# stm32_v0_7_eagle_v7.net
KiCad netlist of a schematic drawn in EAGLE
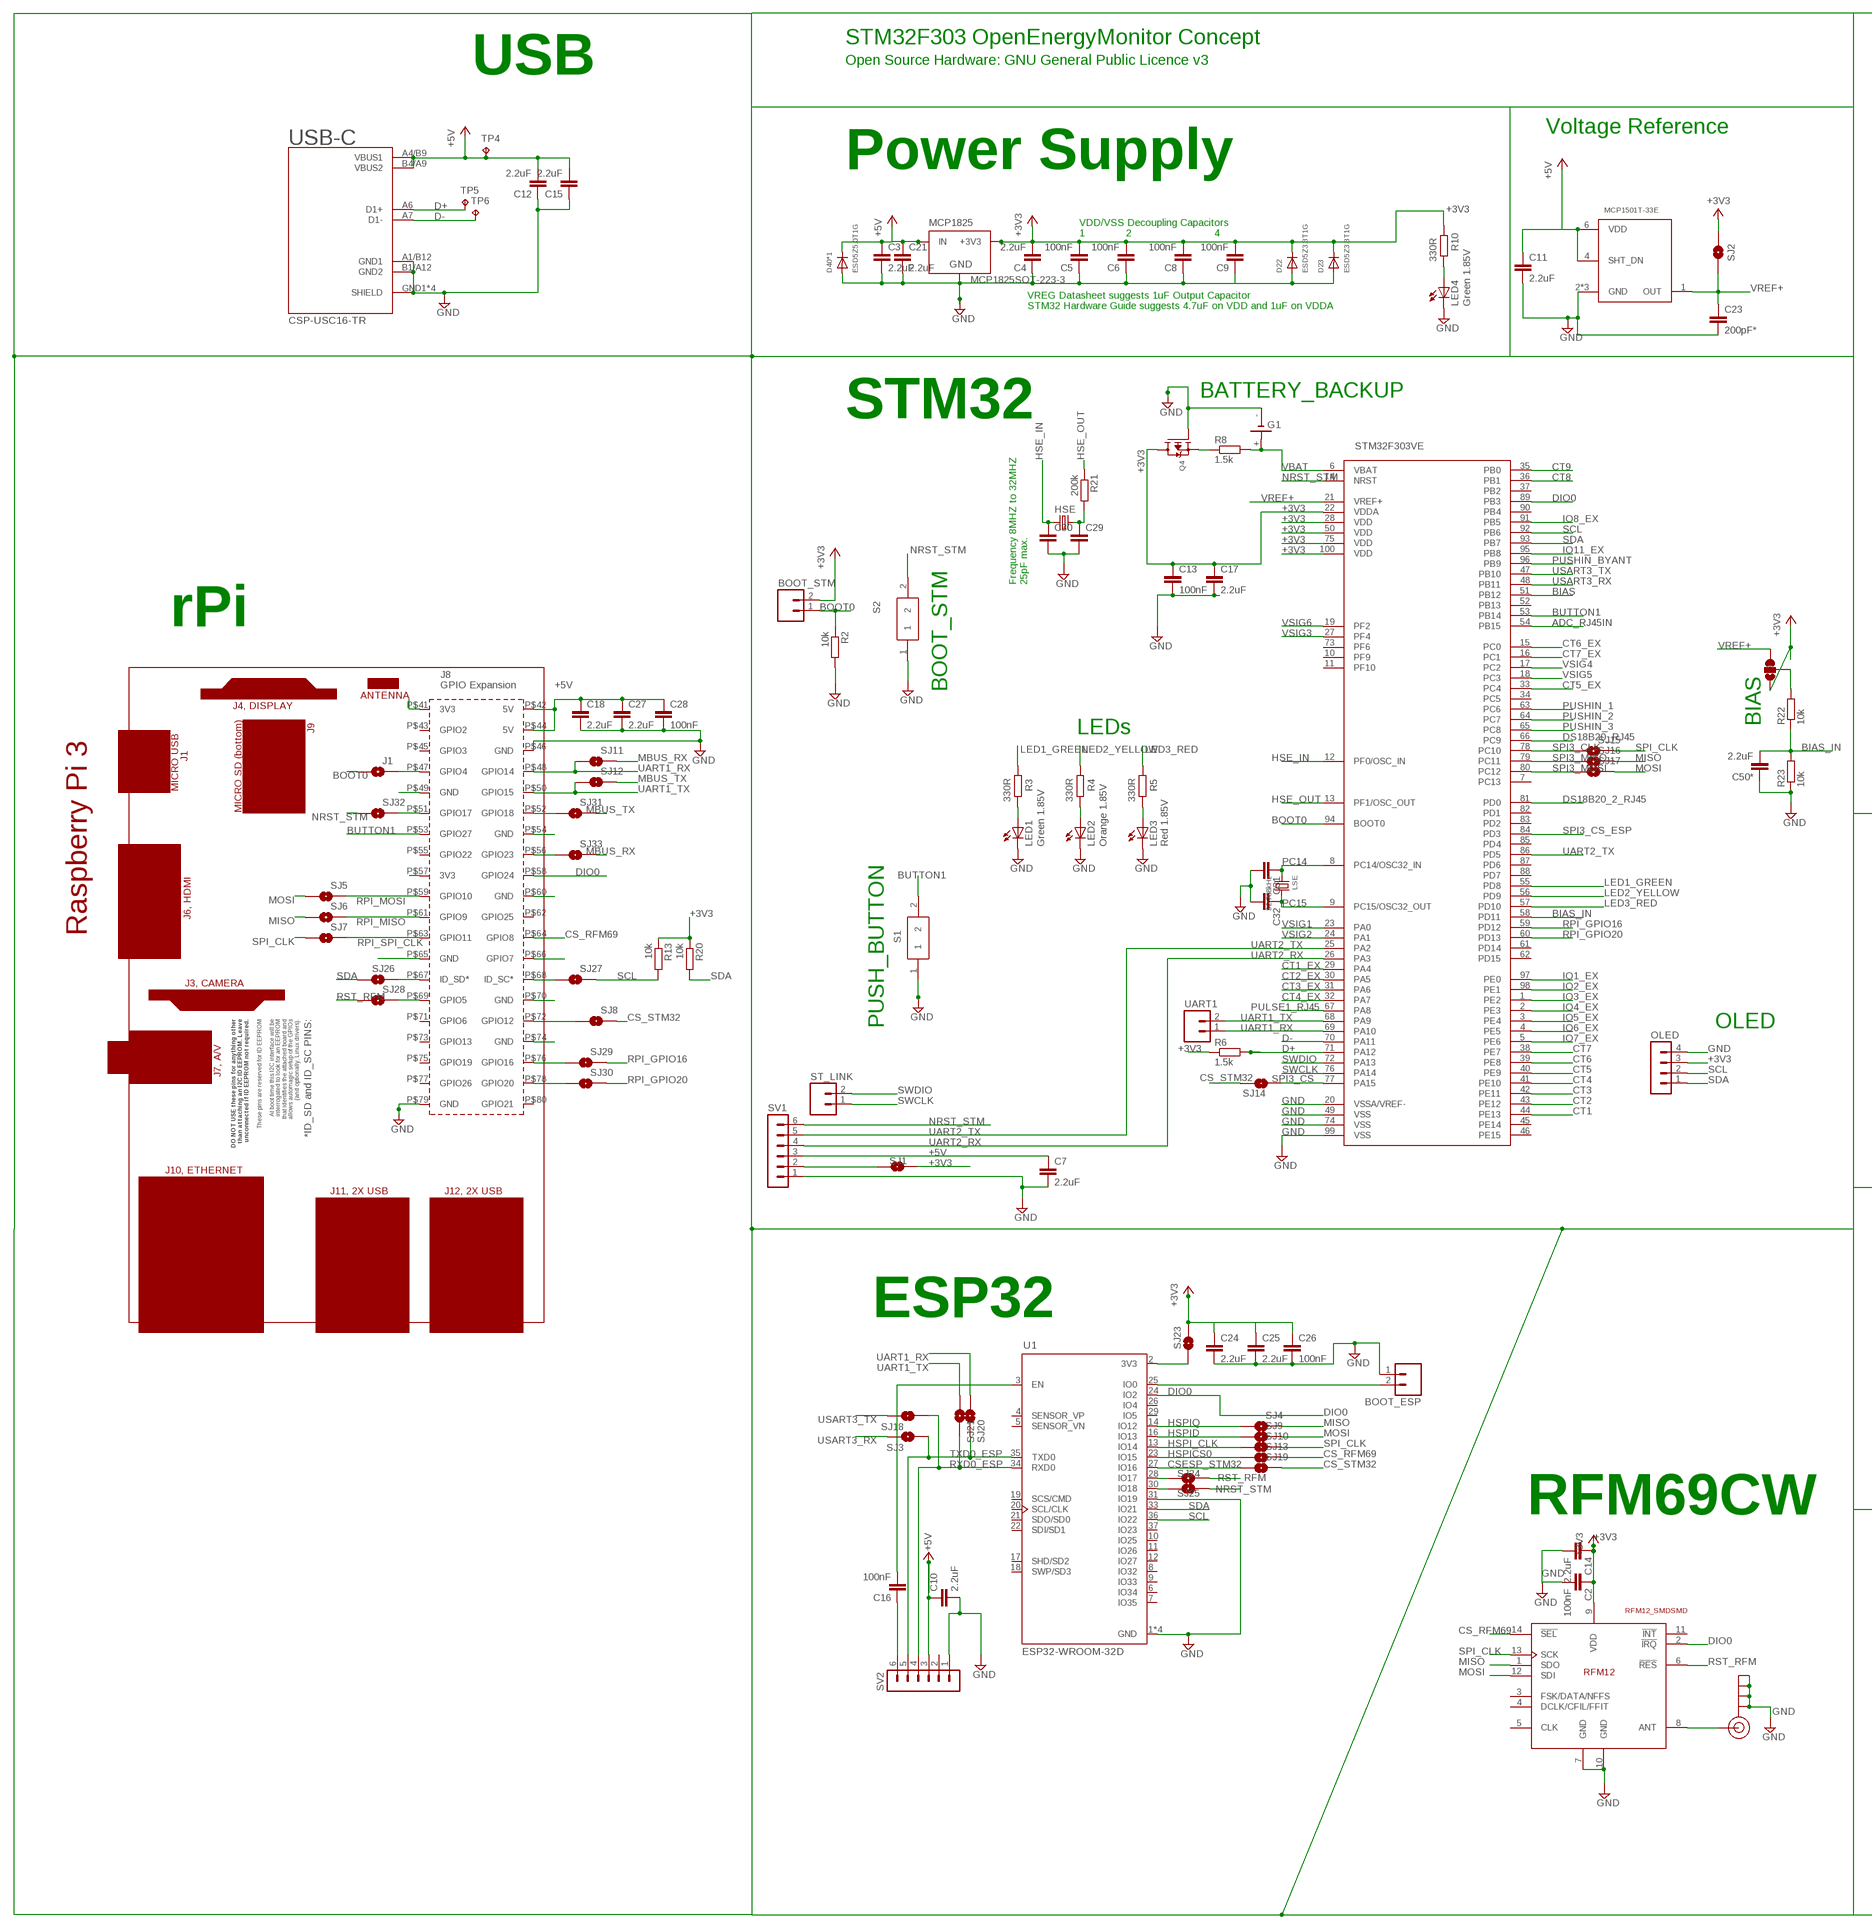
[diagram p0: schematic, sheet 1, part 1 of 2]
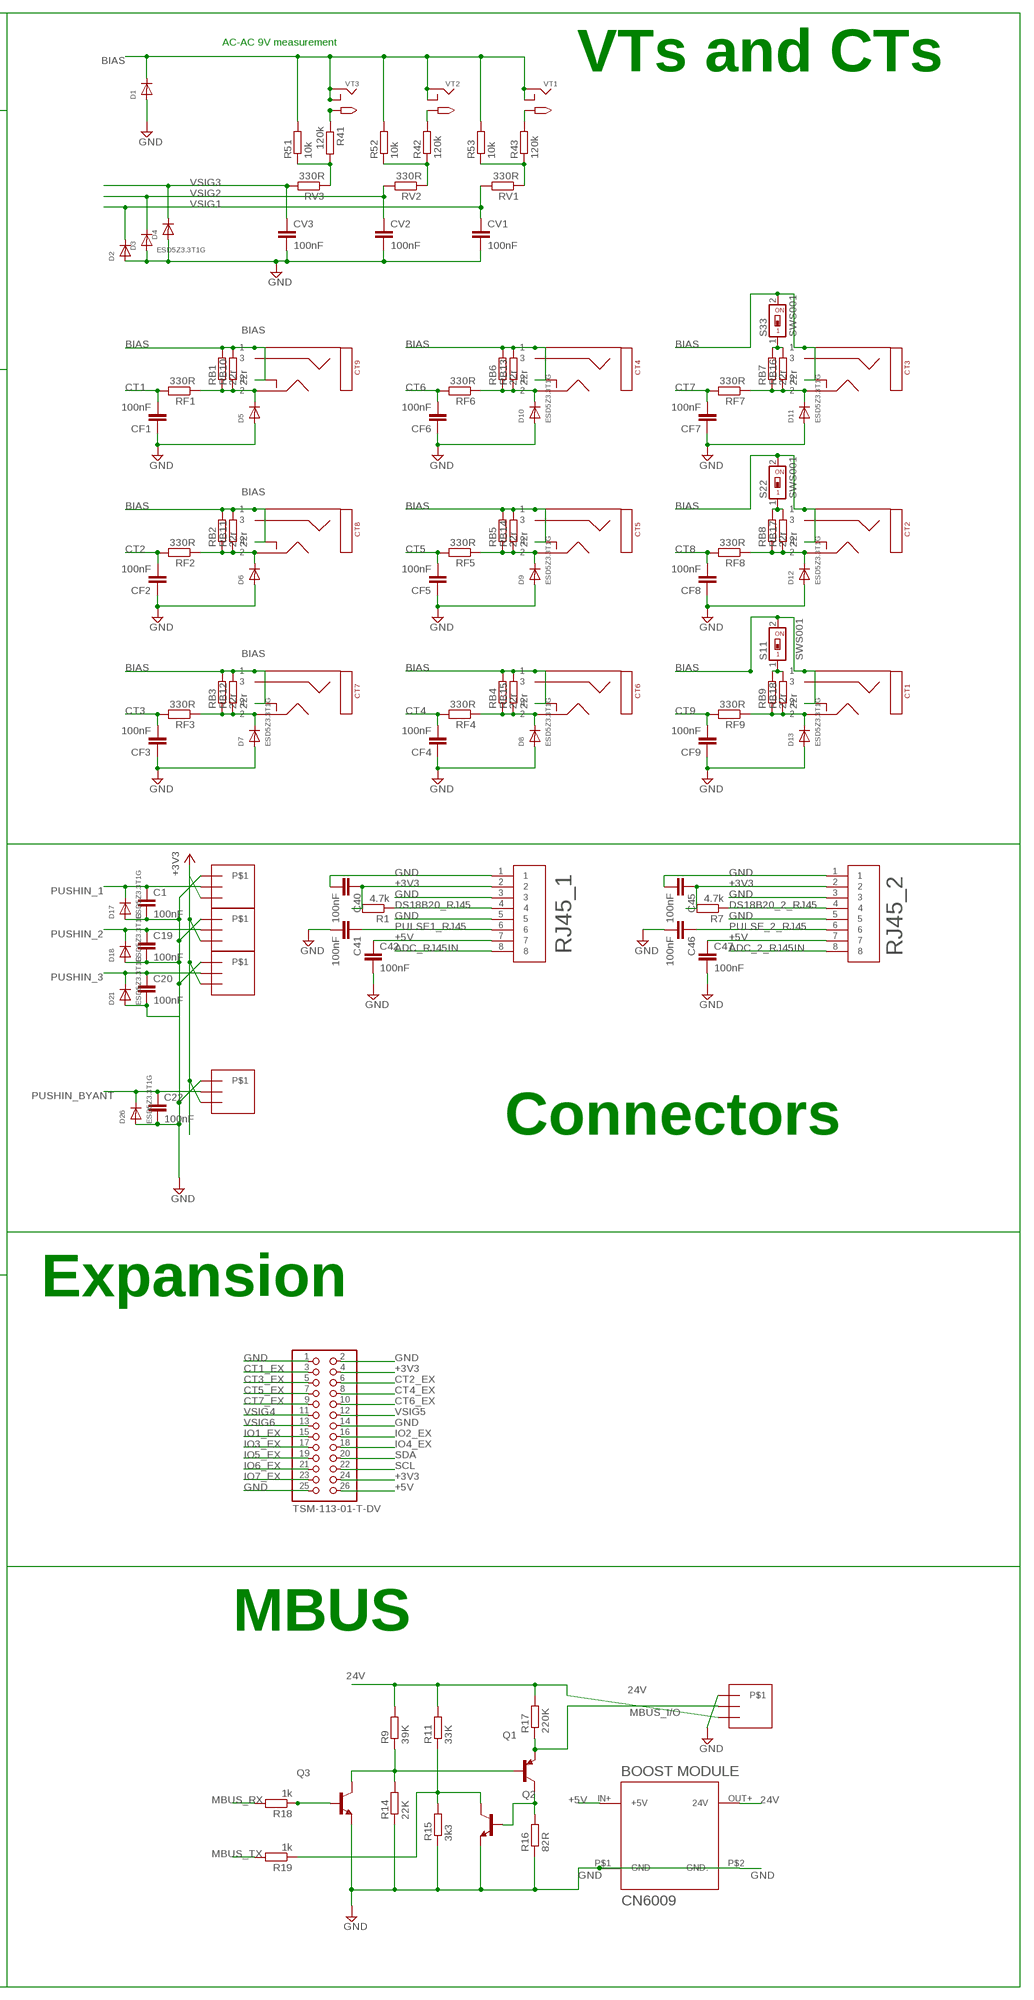
[diagram p1: schematic, sheet 1, part 2 of 2]

(export (version "E")
  (design (tool "Eeschema 10.0.6"))
  (components
    (comp (ref "BOOT_ESP")
      (value "M02PTH")
      (footprint "eagle-import:1X02")
      (libsource (lib "eagle-import") (part "M02PTH"))
    )
    (comp (ref "BOOT_STM")
      (value "M02PTH")
      (footprint "eagle-import:1X02")
      (libsource (lib "eagle-import") (part "M02PTH"))
    )
    (comp (ref "C1")
      (value "100nF")
      (footprint "eagle-import:C0603")
      (libsource (lib "eagle-import") (part "resistor_C-EUC0603"))
    )
    (comp (ref "C2")
      (value "100nF")
      (footprint "eagle-import:C0603")
      (libsource (lib "eagle-import") (part "resistor_C-EUC0603"))
    )
    (comp (ref "C3")
      (value "2.2uF")
      (footprint "eagle-import:C0805")
      (libsource (lib "eagle-import") (part "C-EUC0805"))
    )
    (comp (ref "C4")
      (value "2.2uF")
      (footprint "eagle-import:C0805")
      (libsource (lib "eagle-import") (part "C-EUC0805"))
    )
    (comp (ref "C5")
      (value "100nF")
      (footprint "eagle-import:C0603")
      (libsource (lib "eagle-import") (part "resistor_C-EUC0603"))
    )
    (comp (ref "C6")
      (value "100nF")
      (footprint "eagle-import:C0603")
      (libsource (lib "eagle-import") (part "resistor_C-EUC0603"))
    )
    (comp (ref "C7")
      (value "2.2uF")
      (footprint "eagle-import:C0805")
      (libsource (lib "eagle-import") (part "C-EUC0805"))
    )
    (comp (ref "C8")
      (value "100nF")
      (footprint "eagle-import:C0603")
      (libsource (lib "eagle-import") (part "resistor_C-EUC0603"))
    )
    (comp (ref "C9")
      (value "100nF")
      (footprint "eagle-import:C0603")
      (libsource (lib "eagle-import") (part "resistor_C-EUC0603"))
    )
    (comp (ref "C10")
      (value "2.2uF")
      (footprint "eagle-import:C0805")
      (libsource (lib "eagle-import") (part "C-EUC0805"))
    )
    (comp (ref "C11")
      (value "2.2uF")
      (footprint "eagle-import:C0805")
      (libsource (lib "eagle-import") (part "C-EUC0805"))
    )
    (comp (ref "C12")
      (value "2.2uF")
      (footprint "eagle-import:C0805")
      (libsource (lib "eagle-import") (part "C-EUC0805"))
    )
    (comp (ref "C13")
      (value "100nF")
      (footprint "eagle-import:C0603")
      (libsource (lib "eagle-import") (part "C-EUC0603"))
    )
    (comp (ref "C14")
      (value "2.2uF")
      (footprint "eagle-import:C0805")
      (libsource (lib "eagle-import") (part "C-EUC0805"))
    )
    (comp (ref "C15")
      (value "2.2uF")
      (footprint "eagle-import:C0805")
      (libsource (lib "eagle-import") (part "C-EUC0805"))
    )
    (comp (ref "C16")
      (value "100nF")
      (footprint "eagle-import:C0603")
      (libsource (lib "eagle-import") (part "resistor_C-EUC0603"))
    )
    (comp (ref "C17")
      (value "2.2uF")
      (footprint "eagle-import:C0805")
      (libsource (lib "eagle-import") (part "C-EUC0805"))
    )
    (comp (ref "C18")
      (value "2.2uF")
      (footprint "eagle-import:C0805")
      (libsource (lib "eagle-import") (part "C-EUC0805"))
    )
    (comp (ref "C19")
      (value "100nF")
      (footprint "eagle-import:C0603")
      (libsource (lib "eagle-import") (part "resistor_C-EUC0603"))
    )
    (comp (ref "C20")
      (value "100nF")
      (footprint "eagle-import:C0603")
      (libsource (lib "eagle-import") (part "resistor_C-EUC0603"))
    )
    (comp (ref "C21")
      (value "2.2uF")
      (footprint "eagle-import:C0805")
      (libsource (lib "eagle-import") (part "C-EUC0805"))
    )
    (comp (ref "C22")
      (value "100nF")
      (footprint "eagle-import:C0603")
      (libsource (lib "eagle-import") (part "resistor_C-EUC0603"))
    )
    (comp (ref "C23")
      (value "200pF*")
      (footprint "eagle-import:C0603")
      (libsource (lib "eagle-import") (part "C-EUC0603"))
    )
    (comp (ref "C24")
      (value "2.2uF")
      (footprint "eagle-import:C0805")
      (libsource (lib "eagle-import") (part "C-EUC0805"))
    )
    (comp (ref "C25")
      (value "2.2uF")
      (footprint "eagle-import:C0805")
      (libsource (lib "eagle-import") (part "C-EUC0805"))
    )
    (comp (ref "C26")
      (value "100nF")
      (footprint "eagle-import:C0603")
      (libsource (lib "eagle-import") (part "resistor_C-EUC0603"))
    )
    (comp (ref "C27")
      (value "2.2uF")
      (footprint "eagle-import:C0805")
      (libsource (lib "eagle-import") (part "C-EUC0805"))
    )
    (comp (ref "C28")
      (value "100nF")
      (footprint "eagle-import:C0603")
      (libsource (lib "eagle-import") (part "resistor_C-EUC0603"))
    )
    (comp (ref "C29")
      (value "5nF")
      (footprint "eagle-import:C0603")
      (libsource (lib "eagle-import") (part "C-EUC0603"))
    )
    (comp (ref "C30")
      (value "5nF")
      (footprint "eagle-import:C0603")
      (libsource (lib "eagle-import") (part "C-EUC0603"))
    )
    (comp (ref "C31")
      (value "2.2uF")
      (footprint "eagle-import:C0805")
      (libsource (lib "eagle-import") (part "C-EUC0805"))
    )
    (comp (ref "C32")
      (value "2.2uF")
      (footprint "eagle-import:C0805")
      (libsource (lib "eagle-import") (part "C-EUC0805"))
    )
    (comp (ref "C40")
      (value "100nF")
      (footprint "eagle-import:C0603")
      (libsource (lib "eagle-import") (part "resistor_C-EUC0603"))
    )
    (comp (ref "C41")
      (value "100nF")
      (footprint "eagle-import:C0603")
      (libsource (lib "eagle-import") (part "resistor_C-EUC0603"))
    )
    (comp (ref "C42")
      (value "100nF")
      (footprint "eagle-import:C0603")
      (libsource (lib "eagle-import") (part "resistor_C-EUC0603"))
    )
    (comp (ref "C45")
      (value "100nF")
      (footprint "eagle-import:C0603")
      (libsource (lib "eagle-import") (part "resistor_C-EUC0603"))
    )
    (comp (ref "C46")
      (value "100nF")
      (footprint "eagle-import:C0603")
      (libsource (lib "eagle-import") (part "resistor_C-EUC0603"))
    )
    (comp (ref "C47")
      (value "100nF")
      (footprint "eagle-import:C0603")
      (libsource (lib "eagle-import") (part "resistor_C-EUC0603"))
    )
    (comp (ref "C50*")
      (value "2.2uF")
      (footprint "eagle-import:C0805")
      (libsource (lib "eagle-import") (part "C-EUC0805"))
    )
    (comp (ref "CF1")
      (value "100nF")
      (footprint "eagle-import:C0603")
      (libsource (lib "eagle-import") (part "resistor_C-EUC0603"))
    )
    (comp (ref "CF2")
      (value "100nF")
      (footprint "eagle-import:C0603")
      (libsource (lib "eagle-import") (part "resistor_C-EUC0603"))
    )
    (comp (ref "CF3")
      (value "100nF")
      (footprint "eagle-import:C0603")
      (libsource (lib "eagle-import") (part "resistor_C-EUC0603"))
    )
    (comp (ref "CF4")
      (value "100nF")
      (footprint "eagle-import:C0603")
      (libsource (lib "eagle-import") (part "resistor_C-EUC0603"))
    )
    (comp (ref "CF5")
      (value "100nF")
      (footprint "eagle-import:C0603")
      (libsource (lib "eagle-import") (part "resistor_C-EUC0603"))
    )
    (comp (ref "CF6")
      (value "100nF")
      (footprint "eagle-import:C0603")
      (libsource (lib "eagle-import") (part "resistor_C-EUC0603"))
    )
    (comp (ref "CF7")
      (value "100nF")
      (footprint "eagle-import:C0603")
      (libsource (lib "eagle-import") (part "resistor_C-EUC0603"))
    )
    (comp (ref "CF8")
      (value "100nF")
      (footprint "eagle-import:C0603")
      (libsource (lib "eagle-import") (part "resistor_C-EUC0603"))
    )
    (comp (ref "CF9")
      (value "100nF")
      (footprint "eagle-import:C0603")
      (libsource (lib "eagle-import") (part "resistor_C-EUC0603"))
    )
    (comp (ref "CT1")
      (value "SJ-3523-SMT")
      (footprint "eagle-import:STEREO_SMT")
      (libsource (lib "eagle-import") (part "STEREO_SMD"))
    )
    (comp (ref "CT2")
      (value "SJ-3523-SMT")
      (footprint "eagle-import:STEREO_SMT")
      (libsource (lib "eagle-import") (part "STEREO_SMD"))
    )
    (comp (ref "CT3")
      (value "SJ-3523-SMT")
      (footprint "eagle-import:STEREO_SMT")
      (libsource (lib "eagle-import") (part "STEREO_SMD"))
    )
    (comp (ref "CT4")
      (value "SJ-3523-SMT")
      (footprint "eagle-import:STEREO_SMT")
      (libsource (lib "eagle-import") (part "STEREO_SMD"))
    )
    (comp (ref "CT5")
      (value "SJ-3523-SMT")
      (footprint "eagle-import:STEREO_SMT")
      (libsource (lib "eagle-import") (part "STEREO_SMD"))
    )
    (comp (ref "CT6")
      (value "SJ-3523-SMT")
      (footprint "eagle-import:STEREO_SMT")
      (libsource (lib "eagle-import") (part "STEREO_SMD"))
    )
    (comp (ref "CT7")
      (value "SJ-3523-SMT")
      (footprint "eagle-import:STEREO_SMT")
      (libsource (lib "eagle-import") (part "STEREO_SMD"))
    )
    (comp (ref "CT8")
      (value "SJ-3523-SMT")
      (footprint "eagle-import:STEREO_SMT")
      (libsource (lib "eagle-import") (part "STEREO_SMD"))
    )
    (comp (ref "CT9")
      (value "SJ-3523-SMT")
      (footprint "eagle-import:STEREO_SMT")
      (libsource (lib "eagle-import") (part "STEREO_SMD"))
    )
    (comp (ref "CV1")
      (value "100nF")
      (footprint "eagle-import:C0603")
      (libsource (lib "eagle-import") (part "resistor_C-EUC0603"))
    )
    (comp (ref "CV2")
      (value "100nF")
      (footprint "eagle-import:C0603")
      (libsource (lib "eagle-import") (part "resistor_C-EUC0603"))
    )
    (comp (ref "CV3")
      (value "100nF")
      (footprint "eagle-import:C0603")
      (libsource (lib "eagle-import") (part "resistor_C-EUC0603"))
    )
    (comp (ref "D1")
      (value "ESD5Z3.3T1G")
      (footprint "eagle-import:SOD-523")
      (libsource (lib "eagle-import") (part "DIODESOD-523"))
    )
    (comp (ref "D2")
      (value "ESD5Z3.3T1G")
      (footprint "eagle-import:SOD-523")
      (libsource (lib "eagle-import") (part "DIODESOD-523"))
    )
    (comp (ref "D3")
      (value "ESD5Z3.3T1G")
      (footprint "eagle-import:SOD-523")
      (libsource (lib "eagle-import") (part "DIODESOD-523"))
    )
    (comp (ref "D4")
      (value "ESD5Z3.3T1G")
      (footprint "eagle-import:SOD-523")
      (libsource (lib "eagle-import") (part "DIODESOD-523"))
    )
    (comp (ref "D5")
      (value "ESD5Z3.3T1G")
      (footprint "eagle-import:SOD-523")
      (libsource (lib "eagle-import") (part "DIODESOD-523"))
    )
    (comp (ref "D6")
      (value "ESD5Z3.3T1G")
      (footprint "eagle-import:SOD-523")
      (libsource (lib "eagle-import") (part "DIODESOD-523"))
    )
    (comp (ref "D7")
      (value "ESD5Z3.3T1G")
      (footprint "eagle-import:SOD-523")
      (libsource (lib "eagle-import") (part "DIODESOD-523"))
    )
    (comp (ref "D8")
      (value "ESD5Z3.3T1G")
      (footprint "eagle-import:SOD-523")
      (libsource (lib "eagle-import") (part "DIODESOD-523"))
    )
    (comp (ref "D9")
      (value "ESD5Z3.3T1G")
      (footprint "eagle-import:SOD-523")
      (libsource (lib "eagle-import") (part "DIODESOD-523"))
    )
    (comp (ref "D10")
      (value "ESD5Z3.3T1G")
      (footprint "eagle-import:SOD-523")
      (libsource (lib "eagle-import") (part "DIODESOD-523"))
    )
    (comp (ref "D11")
      (value "ESD5Z3.3T1G")
      (footprint "eagle-import:SOD-523")
      (libsource (lib "eagle-import") (part "DIODESOD-523"))
    )
    (comp (ref "D12")
      (value "ESD5Z3.3T1G")
      (footprint "eagle-import:SOD-523")
      (libsource (lib "eagle-import") (part "DIODESOD-523"))
    )
    (comp (ref "D13")
      (value "ESD5Z3.3T1G")
      (footprint "eagle-import:SOD-523")
      (libsource (lib "eagle-import") (part "DIODESOD-523"))
    )
    (comp (ref "D17")
      (value "ESD5Z3.3T1G")
      (footprint "eagle-import:SOD-523")
      (libsource (lib "eagle-import") (part "DIODESOD-523"))
    )
    (comp (ref "D18")
      (value "ESD5Z3.3T1G")
      (footprint "eagle-import:SOD-523")
      (libsource (lib "eagle-import") (part "DIODESOD-523"))
    )
    (comp (ref "D21")
      (value "ESD5Z3.3T1G")
      (footprint "eagle-import:SOD-523")
      (libsource (lib "eagle-import") (part "DIODESOD-523"))
    )
    (comp (ref "D22")
      (value "ESD5Z3.3T1G")
      (footprint "eagle-import:SOD-523")
      (libsource (lib "eagle-import") (part "DIODESOD-523"))
    )
    (comp (ref "D23")
      (value "ESD5Z3.3T1G")
      (footprint "eagle-import:SOD-523")
      (libsource (lib "eagle-import") (part "DIODESOD-523"))
    )
    (comp (ref "D26")
      (value "ESD5Z3.3T1G")
      (footprint "eagle-import:SOD-523")
      (libsource (lib "eagle-import") (part "DIODESOD-523"))
    )
    (comp (ref "D40*1")
      (value "ESD5Z5.0T1G")
      (footprint "eagle-import:SOD-523")
      (libsource (lib "eagle-import") (part "DIODESOD-523"))
    )
    (comp (ref "EXPANSION")
      (value "TSM-113-01-T-DV")
      (footprint "eagle-import:2X13_SMT")
      (libsource (lib "eagle-import") (part "PINHD-2X13SMT"))
    )
    (comp (ref "G1")
      (value "CH291-1220LF")
      (footprint "eagle-import:CH291-1220LF")
      (fields (field (name "MF") "Multicomp"))
      (libsource (lib "eagle-import") (part "CH291-1220LF"))
    )
    (comp (ref "HSE")
      (value "406C35E08M00000")
      (footprint "eagle-import:CTS406")
      (libsource (lib "eagle-import") (part "CRYSTALCTS406"))
    )
    (comp (ref "J$1")
      (value "SMA_EDGE")
      (footprint "eagle-import:SMA-EDGE")
      (libsource (lib "eagle-import") (part "SMA_EDGE"))
    )
    (comp (ref "J1")
      (value "SOLDERJUMPERNO")
      (footprint "eagle-import:SJ_2S-NO")
      (libsource (lib "eagle-import") (part "SOLDERJUMPERNO"))
    )
    (comp (ref "JP1")
      (value "JUMPER-SMT_3_1-NC_TRACE_NO-SILK")
      (footprint "eagle-import:SMT-JUMPER_3_1-NC_TRACE_NO-SILK")
      (libsource (lib "eagle-import") (part "JUMPER-SMT_3_1-NC_TRACE_NO-SILK"))
    )
    (comp (ref "LED1")
      (value "Green 1.85V")
      (footprint "eagle-import:CHIP-LED0805")
      (libsource (lib "eagle-import") (part "LEDCHIP-LED0805"))
    )
    (comp (ref "LED2")
      (value "Orange 1.85V")
      (footprint "eagle-import:CHIP-LED0805")
      (libsource (lib "eagle-import") (part "LEDCHIP-LED0805"))
    )
    (comp (ref "LED3")
      (value "Red 1.85V")
      (footprint "eagle-import:CHIP-LED0805")
      (libsource (lib "eagle-import") (part "LEDCHIP-LED0805"))
    )
    (comp (ref "LED4")
      (value "Green 1.85V")
      (footprint "eagle-import:CHIP-LED0805")
      (libsource (lib "eagle-import") (part "LEDCHIP-LED0805"))
    )
    (comp (ref "LSE")
      (value "32.768kHz")
      (footprint "eagle-import:CRYSTAL_8X3.8")
      (libsource (lib "eagle-import") (part "CRYSTAL8X3.8SMT"))
    )
    (comp (ref "MCP1825")
      (value "MCP1825SOT-223-3")
      (footprint "eagle-import:SOT-223")
      (libsource (lib "eagle-import") (part "MCP1825SOT-223-3"))
    )
    (comp (ref "OLED")
      (value "MA04-1-OLEDOLED")
      (footprint "eagle-import:MA04-1-OLED")
      (libsource (lib "eagle-import") (part "MA04-1-OLEDOLED"))
    )
    (comp (ref "PCB2")
      (value "TSM-120-01-T-DV")
      (footprint "eagle-import:RPI3MIRROR2")
      (libsource (lib "eagle-import") (part "RPI3YA"))
    )
    (comp (ref "Q1")
      (value "MMBT3906")
      (footprint "eagle-import:SOT23")
      (fields
        (field (name "DIGIKEY_PART_NUMBER") "MMBT3906FSCT-ND")
        (field (name "MANUFACTURER") "ON Semiconductor")
        (field (name "CREATED_BY") "PCB Layout")
      )
      (libsource (lib "eagle-import") (part "MMBT3906"))
    )
    (comp (ref "Q2")
      (value "MMBT3904")
      (footprint "eagle-import:SOT23")
      (fields
        (field (name "DIGIKEY_PART_NUMBER") "MMBT3904FSCT-ND")
        (field (name "MANUFACTURER") "ON Semiconductor")
        (field (name "CREATED_BY") "PCB Layout")
      )
      (libsource (lib "eagle-import") (part "MMBT3904"))
    )
    (comp (ref "Q3")
      (value "MMBT3904")
      (footprint "eagle-import:SOT23")
      (fields
        (field (name "DIGIKEY_PART_NUMBER") "MMBT3904FSCT-ND")
        (field (name "MANUFACTURER") "ON Semiconductor")
        (field (name "CREATED_BY") "PCB Layout")
      )
      (libsource (lib "eagle-import") (part "MMBT3904"))
    )
    (comp (ref "Q4")
      (value "MOSFET-P")
      (footprint "eagle-import:SOT23-R")
      (libsource (lib "eagle-import") (part "MOSFET-P"))
    )
    (comp (ref "R1")
      (value "4.7k")
      (footprint "eagle-import:R0603")
      (libsource (lib "eagle-import") (part "resistor_R-EU_R0603"))
    )
    (comp (ref "R2")
      (value "10k")
      (footprint "eagle-import:R0603")
      (libsource (lib "eagle-import") (part "resistor_R-EU_R0603"))
    )
    (comp (ref "R3")
      (value "330R")
      (footprint "eagle-import:R0603")
      (libsource (lib "eagle-import") (part "R-EU_R0603"))
    )
    (comp (ref "R4")
      (value "330R")
      (footprint "eagle-import:R0603")
      (libsource (lib "eagle-import") (part "R-EU_R0603"))
    )
    (comp (ref "R5")
      (value "330R")
      (footprint "eagle-import:R0603")
      (libsource (lib "eagle-import") (part "R-EU_R0603"))
    )
    (comp (ref "R6")
      (value "1.5k")
      (footprint "eagle-import:R0603")
      (libsource (lib "eagle-import") (part "R-EU_R0603"))
    )
    (comp (ref "R7")
      (value "4.7k")
      (footprint "eagle-import:R0603")
      (libsource (lib "eagle-import") (part "resistor_R-EU_R0603"))
    )
    (comp (ref "R8")
      (value "1.5k")
      (footprint "eagle-import:R0603")
      (libsource (lib "eagle-import") (part "resistor_R-EU_R0603"))
    )
    (comp (ref "R9")
      (value "39K")
      (footprint "eagle-import:R0603")
      (libsource (lib "eagle-import") (part "R-EU_R0603"))
    )
    (comp (ref "R10")
      (value "330R")
      (footprint "eagle-import:R0603")
      (libsource (lib "eagle-import") (part "R-EU_R0603"))
    )
    (comp (ref "R11")
      (value "33K")
      (footprint "eagle-import:R0603")
      (libsource (lib "eagle-import") (part "R-EU_R0603"))
    )
    (comp (ref "R13")
      (value "10k")
      (footprint "eagle-import:R0603")
      (libsource (lib "eagle-import") (part "resistor_R-EU_R0603"))
    )
    (comp (ref "R14")
      (value "22K")
      (footprint "eagle-import:R0603")
      (libsource (lib "eagle-import") (part "R-EU_R0603"))
    )
    (comp (ref "R15")
      (value "3k3")
      (footprint "eagle-import:R0603")
      (libsource (lib "eagle-import") (part "R-EU_R0603"))
    )
    (comp (ref "R16")
      (value "82R")
      (footprint "eagle-import:R0603")
      (libsource (lib "eagle-import") (part "R-EU_R0603"))
    )
    (comp (ref "R17")
      (value "220K")
      (footprint "eagle-import:R0603")
      (libsource (lib "eagle-import") (part "R-EU_R0603"))
    )
    (comp (ref "R18")
      (value "1k")
      (footprint "eagle-import:R0603")
      (libsource (lib "eagle-import") (part "R-EU_R0603"))
    )
    (comp (ref "R19")
      (value "1k")
      (footprint "eagle-import:R0603")
      (libsource (lib "eagle-import") (part "R-EU_R0603"))
    )
    (comp (ref "R20")
      (value "10k")
      (footprint "eagle-import:R0603")
      (libsource (lib "eagle-import") (part "resistor_R-EU_R0603"))
    )
    (comp (ref "R21")
      (value "200k")
      (footprint "eagle-import:R0603")
      (libsource (lib "eagle-import") (part "resistor_R-EU_R0603"))
    )
    (comp (ref "R22")
      (value "10k")
      (footprint "eagle-import:R0603")
      (libsource (lib "eagle-import") (part "resistor_R-EU_R0603"))
    )
    (comp (ref "R23")
      (value "10k")
      (footprint "eagle-import:R0603")
      (libsource (lib "eagle-import") (part "resistor_R-EU_R0603"))
    )
    (comp (ref "R41")
      (value "120k")
      (footprint "eagle-import:R0603")
      (libsource (lib "eagle-import") (part "resistor_R-EU_R0603"))
    )
    (comp (ref "R42")
      (value "120k")
      (footprint "eagle-import:R0603")
      (libsource (lib "eagle-import") (part "resistor_R-EU_R0603"))
    )
    (comp (ref "R43")
      (value "120k")
      (footprint "eagle-import:R0603")
      (libsource (lib "eagle-import") (part "resistor_R-EU_R0603"))
    )
    (comp (ref "R51")
      (value "10k")
      (footprint "eagle-import:R0603")
      (libsource (lib "eagle-import") (part "resistor_R-EU_R0603"))
    )
    (comp (ref "R52")
      (value "10k")
      (footprint "eagle-import:R0603")
      (libsource (lib "eagle-import") (part "resistor_R-EU_R0603"))
    )
    (comp (ref "R53")
      (value "10k")
      (footprint "eagle-import:R0603")
      (libsource (lib "eagle-import") (part "resistor_R-EU_R0603"))
    )
    (comp (ref "RB1")
      (value "22r")
      (footprint "eagle-import:R1206")
      (libsource (lib "eagle-import") (part "R-EU_R1206"))
    )
    (comp (ref "RB2")
      (value "22r")
      (footprint "eagle-import:R1206")
      (libsource (lib "eagle-import") (part "R-EU_R1206"))
    )
    (comp (ref "RB3")
      (value "22r")
      (footprint "eagle-import:R1206")
      (libsource (lib "eagle-import") (part "R-EU_R1206"))
    )
    (comp (ref "RB4")
      (value "22r")
      (footprint "eagle-import:R1206")
      (libsource (lib "eagle-import") (part "R-EU_R1206"))
    )
    (comp (ref "RB5")
      (value "22r")
      (footprint "eagle-import:R1206")
      (libsource (lib "eagle-import") (part "R-EU_R1206"))
    )
    (comp (ref "RB6")
      (value "22r")
      (footprint "eagle-import:R1206")
      (libsource (lib "eagle-import") (part "R-EU_R1206"))
    )
    (comp (ref "RB7")
      (value "22r")
      (footprint "eagle-import:R1206")
      (libsource (lib "eagle-import") (part "R-EU_R1206"))
    )
    (comp (ref "RB8")
      (value "22r")
      (footprint "eagle-import:R1206")
      (libsource (lib "eagle-import") (part "R-EU_R1206"))
    )
    (comp (ref "RB9")
      (value "22r")
      (footprint "eagle-import:R1206")
      (libsource (lib "eagle-import") (part "R-EU_R1206"))
    )
    (comp (ref "RB10")
      (value "22r")
      (footprint "eagle-import:0207_7")
      (libsource (lib "eagle-import") (part "R-EU_0207/7"))
    )
    (comp (ref "RB11")
      (value "22r")
      (footprint "eagle-import:0207_7")
      (libsource (lib "eagle-import") (part "R-EU_0207/7"))
    )
    (comp (ref "RB12")
      (value "22r")
      (footprint "eagle-import:0207_7")
      (libsource (lib "eagle-import") (part "R-EU_0207/7"))
    )
    (comp (ref "RB13")
      (value "22r")
      (footprint "eagle-import:0207_7")
      (libsource (lib "eagle-import") (part "R-EU_0207/7"))
    )
    (comp (ref "RB14")
      (value "22r")
      (footprint "eagle-import:0207_7")
      (libsource (lib "eagle-import") (part "R-EU_0207/7"))
    )
    (comp (ref "RB15")
      (value "22r")
      (footprint "eagle-import:0207_7")
      (libsource (lib "eagle-import") (part "R-EU_0207/7"))
    )
    (comp (ref "RB16")
      (value "22r")
      (footprint "eagle-import:0207_7")
      (libsource (lib "eagle-import") (part "R-EU_0207/7"))
    )
    (comp (ref "RB17")
      (value "22r")
      (footprint "eagle-import:0207_7")
      (libsource (lib "eagle-import") (part "R-EU_0207/7"))
    )
    (comp (ref "RB18")
      (value "22r")
      (footprint "eagle-import:0207_7")
      (libsource (lib "eagle-import") (part "R-EU_0207/7"))
    )
    (comp (ref "RF1")
      (value "330R")
      (footprint "eagle-import:R0603")
      (libsource (lib "eagle-import") (part "resistor_R-EU_R0603"))
    )
    (comp (ref "RF2")
      (value "330R")
      (footprint "eagle-import:R0603")
      (libsource (lib "eagle-import") (part "resistor_R-EU_R0603"))
    )
    (comp (ref "RF3")
      (value "330R")
      (footprint "eagle-import:R0603")
      (libsource (lib "eagle-import") (part "resistor_R-EU_R0603"))
    )
    (comp (ref "RF4")
      (value "330R")
      (footprint "eagle-import:R0603")
      (libsource (lib "eagle-import") (part "resistor_R-EU_R0603"))
    )
    (comp (ref "RF5")
      (value "330R")
      (footprint "eagle-import:R0603")
      (libsource (lib "eagle-import") (part "resistor_R-EU_R0603"))
    )
    (comp (ref "RF6")
      (value "330R")
      (footprint "eagle-import:R0603")
      (libsource (lib "eagle-import") (part "resistor_R-EU_R0603"))
    )
    (comp (ref "RF7")
      (value "330R")
      (footprint "eagle-import:R0603")
      (libsource (lib "eagle-import") (part "resistor_R-EU_R0603"))
    )
    (comp (ref "RF8")
      (value "330R")
      (footprint "eagle-import:R0603")
      (libsource (lib "eagle-import") (part "resistor_R-EU_R0603"))
    )
    (comp (ref "RF9")
      (value "330R")
      (footprint "eagle-import:R0603")
      (libsource (lib "eagle-import") (part "resistor_R-EU_R0603"))
    )
    (comp (ref "RFM69HCW")
      (value "RFM12_SMDSMD")
      (footprint "eagle-import:RFM12")
      (libsource (lib "eagle-import") (part "RFM12_SMDSMD"))
    )
    (comp (ref "RJ45_1")
      (value "95501-6889")
      (footprint "eagle-import:955016889")
      (fields (field (name "MOUSER_PART_NUMBER") "538-95501-6889") (field (name "RS_PART_NUMBER") "3862738"))
      (libsource (lib "eagle-import") (part "95501-6889"))
    )
    (comp (ref "RJ45_2")
      (value "95501-6889")
      (footprint "eagle-import:955016889")
      (fields (field (name "MOUSER_PART_NUMBER") "538-95501-6889") (field (name "RS_PART_NUMBER") "3862738"))
      (libsource (lib "eagle-import") (part "95501-6889"))
    )
    (comp (ref "RV1")
      (value "330R")
      (footprint "eagle-import:R0603")
      (libsource (lib "eagle-import") (part "resistor_R-EU_R0603"))
    )
    (comp (ref "RV2")
      (value "330R")
      (footprint "eagle-import:R0603")
      (libsource (lib "eagle-import") (part "resistor_R-EU_R0603"))
    )
    (comp (ref "RV3")
      (value "330R")
      (footprint "eagle-import:R0603")
      (libsource (lib "eagle-import") (part "resistor_R-EU_R0603"))
    )
    (comp (ref "S1")
      (value "KSS221GLFS")
      (footprint "eagle-import:KSS")
      (fields (field (name "RS_PART_NUMBER") "7931689P"))
      (libsource (lib "eagle-import") (part "KSS221GLFS"))
    )
    (comp (ref "S2")
      (value "KSS221GLFS")
      (footprint "eagle-import:KSS")
      (fields (field (name "RS_PART_NUMBER") "7931689P"))
      (libsource (lib "eagle-import") (part "KSS221GLFS"))
    )
    (comp (ref "S11")
      (value "SWS001")
      (footprint "eagle-import:SMS-001")
      (libsource (lib "eagle-import") (part "SWS001"))
    )
    (comp (ref "S22")
      (value "SWS001")
      (footprint "eagle-import:SMS-001")
      (libsource (lib "eagle-import") (part "SWS001"))
    )
    (comp (ref "S33")
      (value "SWS001")
      (footprint "eagle-import:SMS-001")
      (libsource (lib "eagle-import") (part "SWS001"))
    )
    (comp (ref "SJ1")
      (value "SOLDERJUMPERNO")
      (footprint "eagle-import:SJ_2S-NO")
      (libsource (lib "eagle-import") (part "SOLDERJUMPERNO"))
    )
    (comp (ref "SJ2")
      (value "SOLDERJUMPERNO")
      (footprint "eagle-import:SJ_2S-NO")
      (libsource (lib "eagle-import") (part "SOLDERJUMPERNO"))
    )
    (comp (ref "SJ3")
      (value "SOLDERJUMPERNO")
      (footprint "eagle-import:SJ_2S-NO")
      (libsource (lib "eagle-import") (part "SOLDERJUMPERNO"))
    )
    (comp (ref "SJ4")
      (value "SOLDERJUMPERNO")
      (footprint "eagle-import:SJ_2S-NO")
      (libsource (lib "eagle-import") (part "SOLDERJUMPERNO"))
    )
    (comp (ref "SJ5")
      (value "SOLDERJUMPERNO")
      (footprint "eagle-import:SJ_2S-NO")
      (libsource (lib "eagle-import") (part "SOLDERJUMPERNO"))
    )
    (comp (ref "SJ6")
      (value "SOLDERJUMPERNO")
      (footprint "eagle-import:SJ_2S-NO")
      (libsource (lib "eagle-import") (part "SOLDERJUMPERNO"))
    )
    (comp (ref "SJ7")
      (value "SOLDERJUMPERNO")
      (footprint "eagle-import:SJ_2S-NO")
      (libsource (lib "eagle-import") (part "SOLDERJUMPERNO"))
    )
    (comp (ref "SJ8")
      (value "SOLDERJUMPERNO")
      (footprint "eagle-import:SJ_2S-NO")
      (libsource (lib "eagle-import") (part "SOLDERJUMPERNO"))
    )
    (comp (ref "SJ9")
      (value "SOLDERJUMPERNO")
      (footprint "eagle-import:SJ_2S-NO")
      (libsource (lib "eagle-import") (part "SOLDERJUMPERNO"))
    )
    (comp (ref "SJ10")
      (value "SOLDERJUMPERNO")
      (footprint "eagle-import:SJ_2S-NO")
      (libsource (lib "eagle-import") (part "SOLDERJUMPERNO"))
    )
    (comp (ref "SJ11")
      (value "SOLDERJUMPERNO")
      (footprint "eagle-import:SJ_2S-NO")
      (libsource (lib "eagle-import") (part "SOLDERJUMPERNO"))
    )
    (comp (ref "SJ12")
      (value "SOLDERJUMPERNO")
      (footprint "eagle-import:SJ_2S-NO")
      (libsource (lib "eagle-import") (part "SOLDERJUMPERNO"))
    )
    (comp (ref "SJ13")
      (value "SOLDERJUMPERNO")
      (footprint "eagle-import:SJ_2S-NO")
      (libsource (lib "eagle-import") (part "SOLDERJUMPERNO"))
    )
    (comp (ref "SJ14")
      (value "SOLDERJUMPERNO")
      (footprint "eagle-import:SJ_2S-NO")
      (libsource (lib "eagle-import") (part "SOLDERJUMPERNO"))
    )
    (comp (ref "SJ15")
      (value "SOLDERJUMPERNO")
      (footprint "eagle-import:SJ_2S-NO")
      (libsource (lib "eagle-import") (part "SOLDERJUMPERNO"))
    )
    (comp (ref "SJ16")
      (value "SOLDERJUMPERNO")
      (footprint "eagle-import:SJ_2S-NO")
      (libsource (lib "eagle-import") (part "SOLDERJUMPERNO"))
    )
    (comp (ref "SJ17")
      (value "SOLDERJUMPERNO")
      (footprint "eagle-import:SJ_2S-NO")
      (libsource (lib "eagle-import") (part "SOLDERJUMPERNO"))
    )
    (comp (ref "SJ18")
      (value "SOLDERJUMPERNO")
      (footprint "eagle-import:SJ_2S-NO")
      (libsource (lib "eagle-import") (part "SOLDERJUMPERNO"))
    )
    (comp (ref "SJ19")
      (value "SOLDERJUMPERNO")
      (footprint "eagle-import:SJ_2S-NO")
      (libsource (lib "eagle-import") (part "SOLDERJUMPERNO"))
    )
    (comp (ref "SJ20")
      (value "SOLDERJUMPERNO")
      (footprint "eagle-import:SJ_2S-NO")
      (libsource (lib "eagle-import") (part "SOLDERJUMPERNO"))
    )
    (comp (ref "SJ21")
      (value "SOLDERJUMPERNO")
      (footprint "eagle-import:SJ_2S-NO")
      (libsource (lib "eagle-import") (part "SOLDERJUMPERNO"))
    )
    (comp (ref "SJ23")
      (value "SOLDERJUMPERNO")
      (footprint "eagle-import:SJ_2S-NO")
      (libsource (lib "eagle-import") (part "SOLDERJUMPERNO"))
    )
    (comp (ref "SJ24")
      (value "SOLDERJUMPERNO")
      (footprint "eagle-import:SJ_2S-NO")
      (libsource (lib "eagle-import") (part "SOLDERJUMPERNO"))
    )
    (comp (ref "SJ25")
      (value "SOLDERJUMPERNO")
      (footprint "eagle-import:SJ_2S-NO")
      (libsource (lib "eagle-import") (part "SOLDERJUMPERNO"))
    )
    (comp (ref "SJ26")
      (value "SOLDERJUMPERNO")
      (footprint "eagle-import:SJ_2S-NO")
      (libsource (lib "eagle-import") (part "SOLDERJUMPERNO"))
    )
    (comp (ref "SJ27")
      (value "SOLDERJUMPERNO")
      (footprint "eagle-import:SJ_2S-NO")
      (libsource (lib "eagle-import") (part "SOLDERJUMPERNO"))
    )
    (comp (ref "SJ28")
      (value "SOLDERJUMPERNO")
      (footprint "eagle-import:SJ_2S-NO")
      (libsource (lib "eagle-import") (part "SOLDERJUMPERNO"))
    )
    (comp (ref "SJ29")
      (value "SOLDERJUMPERNO")
      (footprint "eagle-import:SJ_2S-NO")
      (libsource (lib "eagle-import") (part "SOLDERJUMPERNO"))
    )
    (comp (ref "SJ30")
      (value "SOLDERJUMPERNO")
      (footprint "eagle-import:SJ_2S-NO")
      (libsource (lib "eagle-import") (part "SOLDERJUMPERNO"))
    )
    (comp (ref "SJ31")
      (value "SOLDERJUMPERNO")
      (footprint "eagle-import:SJ_2S-NO")
      (libsource (lib "eagle-import") (part "SOLDERJUMPERNO"))
    )
    (comp (ref "SJ32")
      (value "SOLDERJUMPERNO")
      (footprint "eagle-import:SJ_2S-NO")
      (libsource (lib "eagle-import") (part "SOLDERJUMPERNO"))
    )
    (comp (ref "SJ33")
      (value "SOLDERJUMPERNO")
      (footprint "eagle-import:SJ_2S-NO")
      (libsource (lib "eagle-import") (part "SOLDERJUMPERNO"))
    )
    (comp (ref "STM32F303VE")
      (value "STM32F303VE")
      (footprint "eagle-import:TQFP100")
      (libsource (lib "eagle-import") (part "STM32F303XB"))
    )
    (comp (ref "ST_LINK")
      (value "M02PTH")
      (footprint "eagle-import:1X02")
      (libsource (lib "eagle-import") (part "M02PTH"))
    )
    (comp (ref "SV1")
      (value "MA06-1")
      (footprint "eagle-import:MA06-1")
      (libsource (lib "eagle-import") (part "MA06-1"))
    )
    (comp (ref "SV2")
      (value "MA06-1")
      (footprint "eagle-import:MA06-1")
      (libsource (lib "eagle-import") (part "MA06-1"))
    )
    (comp (ref "TP4")
      (value "TPB1,27")
      (footprint "eagle-import:B1,27")
      (libsource (lib "eagle-import") (part "TPB1,27"))
    )
    (comp (ref "TP5")
      (value "TPB1,27")
      (footprint "eagle-import:B1,27")
      (libsource (lib "eagle-import") (part "TPB1,27"))
    )
    (comp (ref "TP6")
      (value "TPB1,27")
      (footprint "eagle-import:B1,27")
      (libsource (lib "eagle-import") (part "TPB1,27"))
    )
    (comp (ref "U$1")
      (value "3.5MM_TERMINAL_BLOCK")
      (footprint "eagle-import:3.5MM_X3")
      (fields (field (name "MPN") "144-4326"))
      (libsource (lib "eagle-import") (part "3.5MM_TERMINAL_BLOCK"))
    )
    (comp (ref "U$2")
      (value "BOOST_MODULE")
      (footprint "eagle-import:BOOST")
      (libsource (lib "eagle-import") (part "BOOST_MODULE"))
    )
    (comp (ref "U$3")
      (value "3.5MM_TERMINAL_BLOCK")
      (footprint "eagle-import:3.5MM_X3")
      (fields (field (name "MPN") "144-4326"))
      (libsource (lib "eagle-import") (part "3.5MM_TERMINAL_BLOCK"))
    )
    (comp (ref "U$4")
      (value "3.5MM_TERMINAL_BLOCK")
      (footprint "eagle-import:3.5MM_X3")
      (fields (field (name "MPN") "144-4326"))
      (libsource (lib "eagle-import") (part "3.5MM_TERMINAL_BLOCK"))
    )
    (comp (ref "U$5")
      (value "3.5MM_TERMINAL_BLOCK")
      (footprint "eagle-import:3.5MM_X3")
      (fields (field (name "MPN") "144-4326"))
      (libsource (lib "eagle-import") (part "3.5MM_TERMINAL_BLOCK"))
    )
    (comp (ref "U$6")
      (value "3.5MM_TERMINAL_BLOCK")
      (footprint "eagle-import:3.5MM_X3")
      (fields (field (name "MPN") "144-4326"))
      (libsource (lib "eagle-import") (part "3.5MM_TERMINAL_BLOCK"))
    )
    (comp (ref "U1")
      (value "ESP32-WROOM-32D")
      (footprint "eagle-import:MODULE_ESP32-WROOM-32D")
      (fields (field (name "MF") "Espressif Systems"))
      (libsource (lib "eagle-import") (part "ESP32-WROOM-32D"))
    )
    (comp (ref "UART1")
      (value "M02PTH")
      (footprint "eagle-import:1X02")
      (libsource (lib "eagle-import") (part "M02PTH"))
    )
    (comp (ref "USB-C")
      (value "CSP-USC16-TR")
      (footprint "eagle-import:USB-C")
      (libsource (lib "eagle-import") (part "CSP-USC16-TR"))
    )
    (comp (ref "VREF_3V3")
      (value "MCP1501T-33E")
      (footprint "eagle-import:SOT95P280X145-6N")
      (libsource (lib "eagle-import") (part "MCP1501T-33E"))
    )
    (comp (ref "VT1")
      (value "ADC-028-2-T")
      (footprint "eagle-import:DCJACK_2MM_SMT")
      (fields (field (name "MPN") "ADC-028-1-T"))
      (libsource (lib "eagle-import") (part "2.1MMJACKSMT"))
    )
    (comp (ref "VT2")
      (value "ADC-028-2-T")
      (footprint "eagle-import:DCJACK_2MM_SMT")
      (fields (field (name "MPN") "ADC-028-1-T"))
      (libsource (lib "eagle-import") (part "2.1MMJACKSMT"))
    )
    (comp (ref "VT3")
      (value "ADC-028-2-T")
      (footprint "eagle-import:DCJACK_2MM_SMT")
      (fields (field (name "MPN") "ADC-028-1-T"))
      (libsource (lib "eagle-import") (part "2.1MMJACKSMT"))
    )
  )
  (nets
    (net (code "1") (name "+3V3") (class "Default")
      (node (ref "BOOT_STM") (pin "2") (pinfunction "2_2") (pintype "passive"))
      (node (ref "C13") (pin "1") (pinfunction "1_1") (pintype "passive"))
      (node (ref "C14") (pin "1") (pinfunction "1_1") (pintype "passive"))
      (node (ref "C17") (pin "1") (pinfunction "1_1") (pintype "passive"))
      (node (ref "C2") (pin "1") (pinfunction "1_1") (pintype "passive"))
      (node (ref "C24") (pin "1") (pinfunction "1_1") (pintype "passive"))
      (node (ref "C25") (pin "1") (pinfunction "1_1") (pintype "passive"))
      (node (ref "C26") (pin "1") (pinfunction "1_1") (pintype "passive"))
      (node (ref "C4") (pin "2") (pinfunction "2_2") (pintype "passive"))
      (node (ref "C40") (pin "1") (pinfunction "1_1") (pintype "passive"))
      (node (ref "C45") (pin "1") (pinfunction "1_1") (pintype "passive"))
      (node (ref "C5") (pin "2") (pinfunction "2_2") (pintype "passive"))
      (node (ref "C6") (pin "2") (pinfunction "2_2") (pintype "passive"))
      (node (ref "C8") (pin "2") (pinfunction "2_2") (pintype "passive"))
      (node (ref "C9") (pin "2") (pinfunction "2_2") (pintype "passive"))
      (node (ref "D22") (pin "K") (pinfunction "C_K") (pintype "passive"))
      (node (ref "D23") (pin "K") (pinfunction "C_K") (pintype "passive"))
      (node (ref "EXPANSION") (pin "24") (pinfunction "24_24") (pintype "passive"))
      (node (ref "EXPANSION") (pin "4") (pinfunction "4_4") (pintype "passive"))
      (node (ref "JP1") (pin "1") (pinfunction "1_1") (pintype "passive"))
      (node (ref "MCP1825") (pin "3") (pinfunction "+3V3_3") (pintype "power_in"))
      (node (ref "OLED") (pin "3") (pinfunction "3_3") (pintype "passive"))
      (node (ref "Q4") (pin "3") (pinfunction "D_3") (pintype "passive"))
      (node (ref "R1") (pin "2") (pinfunction "2_2") (pintype "passive"))
      (node (ref "R10") (pin "2") (pinfunction "2_2") (pintype "passive"))
      (node (ref "R13") (pin "1") (pinfunction "1_1") (pintype "passive"))
      (node (ref "R20") (pin "1") (pinfunction "1_1") (pintype "passive"))
      (node (ref "R6") (pin "1") (pinfunction "1_1") (pintype "passive"))
      (node (ref "R7") (pin "2") (pinfunction "2_2") (pintype "passive"))
      (node (ref "RFM69HCW") (pin "9") (pinfunction "VDD_9") (pintype "power_in"))
      (node (ref "RJ45_1") (pin "2") (pinfunction "2_2") (pintype "bidirectional"))
      (node (ref "RJ45_2") (pin "2") (pinfunction "2_2") (pintype "bidirectional"))
      (node (ref "SJ1") (pin "2") (pinfunction "2_2") (pintype "passive"))
      (node (ref "SJ2") (pin "1") (pinfunction "1_1") (pintype "passive"))
      (node (ref "SJ23") (pin "2") (pinfunction "2_2") (pintype "passive"))
      (node (ref "STM32F303VE") (pin "100") (pinfunction "VDD_100") (pintype "bidirectional"))
      (node (ref "STM32F303VE") (pin "22") (pinfunction "VDDA_22") (pintype "bidirectional"))
      (node (ref "STM32F303VE") (pin "28") (pinfunction "VDD_28") (pintype "bidirectional"))
      (node (ref "STM32F303VE") (pin "50") (pinfunction "VDD_50") (pintype "bidirectional"))
      (node (ref "STM32F303VE") (pin "75") (pinfunction "VDD_75") (pintype "bidirectional"))
      (node (ref "U$1") (pin "P$1") (pinfunction "P$3_P$1") (pintype "bidirectional"))
      (node (ref "U$3") (pin "P$1") (pinfunction "P$3_P$1") (pintype "bidirectional"))
      (node (ref "U$4") (pin "P$1") (pinfunction "P$3_P$1") (pintype "bidirectional"))
      (node (ref "U$5") (pin "P$1") (pinfunction "P$3_P$1") (pintype "bidirectional"))
    )
    (net (code "2") (name "+5V") (class "Default")
      (node (ref "C10") (pin "1") (pinfunction "1_1") (pintype "passive"))
      (node (ref "C11") (pin "1") (pinfunction "1_1") (pintype "passive"))
      (node (ref "C12") (pin "2") (pinfunction "2_2") (pintype "passive"))
      (node (ref "C15") (pin "2") (pinfunction "2_2") (pintype "passive"))
      (node (ref "C18") (pin "1") (pinfunction "1_1") (pintype "passive"))
      (node (ref "C21") (pin "1") (pinfunction "1_1") (pintype "passive"))
      (node (ref "C27") (pin "1") (pinfunction "1_1") (pintype "passive"))
      (node (ref "C28") (pin "1") (pinfunction "1_1") (pintype "passive"))
      (node (ref "C3") (pin "1") (pinfunction "1_1") (pintype "passive"))
      (node (ref "C42") (pin "1") (pinfunction "1_1") (pintype "passive"))
      (node (ref "C47") (pin "1") (pinfunction "1_1") (pintype "passive"))
      (node (ref "C7") (pin "1") (pinfunction "1_1") (pintype "passive"))
      (node (ref "D40*1") (pin "K") (pinfunction "C_K") (pintype "passive"))
      (node (ref "EXPANSION") (pin "26") (pinfunction "26_26") (pintype "passive"))
      (node (ref "MCP1825") (pin "1") (pinfunction "IN_1") (pintype "power_in"))
      (node (ref "PCB2") (pin "P$42") (pinfunction "5V_P$42") (pintype "bidirectional"))
      (node (ref "PCB2") (pin "P$44") (pinfunction "5V_P$44") (pintype "bidirectional"))
      (node (ref "RJ45_1") (pin "7") (pinfunction "7_7") (pintype "bidirectional"))
      (node (ref "RJ45_2") (pin "7") (pinfunction "7_7") (pintype "bidirectional"))
      (node (ref "SV1") (pin "3") (pinfunction "3_3") (pintype "passive"))
      (node (ref "SV2") (pin "3") (pinfunction "3_3") (pintype "passive"))
      (node (ref "TP4") (pin "TP") (pinfunction "TP_TP") (pintype "input"))
      (node (ref "U$2") (pin "IN+") (pinfunction "+5V_IN+") (pintype "bidirectional"))
      (node (ref "USB-C") (pin "A4/B9") (pinfunction "VBUS1_A4/B9") (pintype "passive"))
      (node (ref "USB-C") (pin "B4/A9") (pinfunction "VBUS2_B4/A9") (pintype "passive"))
      (node (ref "VREF_3V3") (pin "4") (pinfunction "SHT_DN_4") (pintype "bidirectional"))
      (node (ref "VREF_3V3") (pin "6") (pinfunction "VDD_6") (pintype "bidirectional"))
    )
    (net (code "3") (name "/24V") (class "Default")
      (node (ref "R11") (pin "2") (pinfunction "2_2") (pintype "passive"))
      (node (ref "R17") (pin "2") (pinfunction "2_2") (pintype "passive"))
      (node (ref "R9") (pin "2") (pinfunction "2_2") (pintype "passive"))
      (node (ref "U$2") (pin "OUT+") (pinfunction "24V_OUT+") (pintype "bidirectional"))
      (node (ref "U$6") (pin "P$1") (pinfunction "P$3_P$1") (pintype "bidirectional"))
    )
    (net (code "4") (name "/ADC_2_RJ45IN") (class "Default")
      (node (ref "RJ45_2") (pin "8") (pinfunction "8_8") (pintype "bidirectional"))
    )
    (net (code "5") (name "/ADC_RJ45IN") (class "Default")
      (node (ref "RJ45_1") (pin "8") (pinfunction "8_8") (pintype "bidirectional"))
      (node (ref "STM32F303VE") (pin "54") (pinfunction "PB15_54") (pintype "bidirectional"))
    )
    (net (code "6") (name "/BIAS") (class "Default")
      (node (ref "CT1") (pin "P$1") (pinfunction "1_P$1") (pintype "bidirectional"))
      (node (ref "CT1") (pin "P$4") (pinfunction "4_P$4") (pintype "bidirectional"))
      (node (ref "CT2") (pin "P$1") (pinfunction "1_P$1") (pintype "bidirectional"))
      (node (ref "CT2") (pin "P$4") (pinfunction "4_P$4") (pintype "bidirectional"))
      (node (ref "CT3") (pin "P$1") (pinfunction "1_P$1") (pintype "bidirectional"))
      (node (ref "CT3") (pin "P$4") (pinfunction "4_P$4") (pintype "bidirectional"))
      (node (ref "CT4") (pin "P$1") (pinfunction "1_P$1") (pintype "bidirectional"))
      (node (ref "CT4") (pin "P$4") (pinfunction "4_P$4") (pintype "bidirectional"))
      (node (ref "CT5") (pin "P$1") (pinfunction "1_P$1") (pintype "bidirectional"))
      (node (ref "CT5") (pin "P$4") (pinfunction "4_P$4") (pintype "bidirectional"))
      (node (ref "CT6") (pin "P$1") (pinfunction "1_P$1") (pintype "bidirectional"))
      (node (ref "CT6") (pin "P$4") (pinfunction "4_P$4") (pintype "bidirectional"))
      (node (ref "CT7") (pin "P$1") (pinfunction "1_P$1") (pintype "bidirectional"))
      (node (ref "CT7") (pin "P$4") (pinfunction "4_P$4") (pintype "bidirectional"))
      (node (ref "CT8") (pin "P$1") (pinfunction "1_P$1") (pintype "bidirectional"))
      (node (ref "CT8") (pin "P$4") (pinfunction "4_P$4") (pintype "bidirectional"))
      (node (ref "CT9") (pin "P$1") (pinfunction "1_P$1") (pintype "bidirectional"))
      (node (ref "CT9") (pin "P$4") (pinfunction "4_P$4") (pintype "bidirectional"))
      (node (ref "D1") (pin "K") (pinfunction "C_K") (pintype "passive"))
      (node (ref "R51") (pin "2") (pinfunction "2_2") (pintype "passive"))
      (node (ref "R52") (pin "2") (pinfunction "2_2") (pintype "passive"))
      (node (ref "R53") (pin "2") (pinfunction "2_2") (pintype "passive"))
      (node (ref "RB1") (pin "2") (pinfunction "2_2") (pintype "passive"))
      (node (ref "RB10") (pin "2") (pinfunction "2_2") (pintype "passive"))
      (node (ref "RB11") (pin "2") (pinfunction "2_2") (pintype "passive"))
      (node (ref "RB12") (pin "2") (pinfunction "2_2") (pintype "passive"))
      (node (ref "RB13") (pin "2") (pinfunction "2_2") (pintype "passive"))
      (node (ref "RB14") (pin "2") (pinfunction "2_2") (pintype "passive"))
      (node (ref "RB15") (pin "2") (pinfunction "2_2") (pintype "passive"))
      (node (ref "RB2") (pin "2") (pinfunction "2_2") (pintype "passive"))
      (node (ref "RB3") (pin "2") (pinfunction "2_2") (pintype "passive"))
      (node (ref "RB4") (pin "2") (pinfunction "2_2") (pintype "passive"))
      (node (ref "RB5") (pin "2") (pinfunction "2_2") (pintype "passive"))
      (node (ref "RB6") (pin "2") (pinfunction "2_2") (pintype "passive"))
      (node (ref "S11") (pin "2") (pinfunction "2_2") (pintype "passive"))
      (node (ref "S22") (pin "2") (pinfunction "2_2") (pintype "passive"))
      (node (ref "S33") (pin "2") (pinfunction "2_2") (pintype "passive"))
      (node (ref "STM32F303VE") (pin "51") (pinfunction "PB12_51") (pintype "bidirectional"))
      (node (ref "VT1") (pin "GND") (pinfunction "RING_GND") (pintype "bidirectional"))
      (node (ref "VT1") (pin "GNDBREAK") (pinfunction "RING_SW_GNDBREAK") (pintype "bidirectional"))
      (node (ref "VT2") (pin "GND") (pinfunction "RING_GND") (pintype "bidirectional"))
      (node (ref "VT2") (pin "GNDBREAK") (pinfunction "RING_SW_GNDBREAK") (pintype "bidirectional"))
      (node (ref "VT3") (pin "GND") (pinfunction "RING_GND") (pintype "bidirectional"))
      (node (ref "VT3") (pin "GNDBREAK") (pinfunction "RING_SW_GNDBREAK") (pintype "bidirectional"))
    )
    (net (code "7") (name "/BIAS_IN") (class "Default")
      (node (ref "C50*") (pin "2") (pinfunction "2_2") (pintype "passive"))
      (node (ref "R22") (pin "1") (pinfunction "1_1") (pintype "passive"))
      (node (ref "R23") (pin "2") (pinfunction "2_2") (pintype "passive"))
      (node (ref "STM32F303VE") (pin "58") (pinfunction "PD11_58") (pintype "bidirectional"))
    )
    (net (code "8") (name "/BOOT0") (class "Default")
      (node (ref "BOOT_STM") (pin "1") (pinfunction "1_1") (pintype "passive"))
      (node (ref "J1") (pin "1") (pinfunction "1_1") (pintype "passive"))
      (node (ref "R2") (pin "1") (pinfunction "1_1") (pintype "passive"))
      (node (ref "STM32F303VE") (pin "94") (pinfunction "BOOT0_94") (pintype "bidirectional"))
    )
    (net (code "9") (name "/BUTTON1") (class "Default")
      (node (ref "PCB2") (pin "P$53") (pinfunction "GPIO27_P$53") (pintype "bidirectional"))
      (node (ref "S1") (pin "2") (pinfunction "2_2") (pintype "bidirectional"))
      (node (ref "STM32F303VE") (pin "53") (pinfunction "PB14_53") (pintype "bidirectional"))
    )
    (net (code "10") (name "/CSESP_STM32") (class "Default")
      (node (ref "SJ19") (pin "1") (pinfunction "1_1") (pintype "passive"))
      (node (ref "U1") (pin "27") (pinfunction "IO16_27") (pintype "bidirectional"))
    )
    (net (code "11") (name "/CS_RFM69") (class "Default")
      (node (ref "PCB2") (pin "P$64") (pinfunction "GPIO8_P$64") (pintype "bidirectional"))
      (node (ref "RFM69HCW") (pin "14") (pinfunction "~{SEL}_14") (pintype "input"))
      (node (ref "SJ13") (pin "2") (pinfunction "2_2") (pintype "passive"))
    )
    (net (code "12") (name "/CS_STM32") (class "Default")
      (node (ref "SJ14") (pin "1") (pinfunction "1_1") (pintype "passive"))
      (node (ref "SJ19") (pin "2") (pinfunction "2_2") (pintype "passive"))
      (node (ref "SJ8") (pin "2") (pinfunction "2_2") (pintype "passive"))
    )
    (net (code "13") (name "/CT1") (class "Default")
      (node (ref "CF1") (pin "2") (pinfunction "2_2") (pintype "passive"))
      (node (ref "RF1") (pin "2") (pinfunction "2_2") (pintype "passive"))
      (node (ref "STM32F303VE") (pin "44") (pinfunction "PE13_44") (pintype "bidirectional"))
    )
    (net (code "14") (name "/CT1_EX") (class "Default")
      (node (ref "EXPANSION") (pin "3") (pinfunction "3_3") (pintype "passive"))
      (node (ref "STM32F303VE") (pin "29") (pinfunction "PA4_29") (pintype "bidirectional"))
    )
    (net (code "15") (name "/CT2") (class "Default")
      (node (ref "CF2") (pin "2") (pinfunction "2_2") (pintype "passive"))
      (node (ref "RF2") (pin "2") (pinfunction "2_2") (pintype "passive"))
      (node (ref "STM32F303VE") (pin "43") (pinfunction "PE12_43") (pintype "bidirectional"))
    )
    (net (code "16") (name "/CT2_EX") (class "Default")
      (node (ref "EXPANSION") (pin "6") (pinfunction "6_6") (pintype "passive"))
      (node (ref "STM32F303VE") (pin "30") (pinfunction "PA5_30") (pintype "bidirectional"))
    )
    (net (code "17") (name "/CT3") (class "Default")
      (node (ref "CF3") (pin "2") (pinfunction "2_2") (pintype "passive"))
      (node (ref "RF3") (pin "2") (pinfunction "2_2") (pintype "passive"))
      (node (ref "STM32F303VE") (pin "42") (pinfunction "PE11_42") (pintype "bidirectional"))
    )
    (net (code "18") (name "/CT3_EX") (class "Default")
      (node (ref "EXPANSION") (pin "5") (pinfunction "5_5") (pintype "passive"))
      (node (ref "STM32F303VE") (pin "31") (pinfunction "PA6_31") (pintype "bidirectional"))
    )
    (net (code "19") (name "/CT4") (class "Default")
      (node (ref "CF4") (pin "2") (pinfunction "2_2") (pintype "passive"))
      (node (ref "RF4") (pin "2") (pinfunction "2_2") (pintype "passive"))
      (node (ref "STM32F303VE") (pin "41") (pinfunction "PE10_41") (pintype "bidirectional"))
    )
    (net (code "20") (name "/CT4_EX") (class "Default")
      (node (ref "EXPANSION") (pin "8") (pinfunction "8_8") (pintype "passive"))
      (node (ref "STM32F303VE") (pin "32") (pinfunction "PA7_32") (pintype "bidirectional"))
    )
    (net (code "21") (name "/CT5") (class "Default")
      (node (ref "CF5") (pin "2") (pinfunction "2_2") (pintype "passive"))
      (node (ref "RF5") (pin "2") (pinfunction "2_2") (pintype "passive"))
      (node (ref "STM32F303VE") (pin "40") (pinfunction "PE9_40") (pintype "bidirectional"))
    )
    (net (code "22") (name "/CT5_EX") (class "Default")
      (node (ref "EXPANSION") (pin "7") (pinfunction "7_7") (pintype "passive"))
      (node (ref "STM32F303VE") (pin "33") (pinfunction "PC4_33") (pintype "bidirectional"))
    )
    (net (code "23") (name "/CT6") (class "Default")
      (node (ref "CF6") (pin "2") (pinfunction "2_2") (pintype "passive"))
      (node (ref "RF6") (pin "2") (pinfunction "2_2") (pintype "passive"))
      (node (ref "STM32F303VE") (pin "39") (pinfunction "PE8_39") (pintype "bidirectional"))
    )
    (net (code "24") (name "/CT6_EX") (class "Default")
      (node (ref "EXPANSION") (pin "10") (pinfunction "10_10") (pintype "passive"))
      (node (ref "STM32F303VE") (pin "15") (pinfunction "PC0_15") (pintype "bidirectional"))
    )
    (net (code "25") (name "/CT7") (class "Default")
      (node (ref "CF7") (pin "2") (pinfunction "2_2") (pintype "passive"))
      (node (ref "RF7") (pin "2") (pinfunction "2_2") (pintype "passive"))
      (node (ref "STM32F303VE") (pin "38") (pinfunction "PE7_38") (pintype "bidirectional"))
    )
    (net (code "26") (name "/CT7_EX") (class "Default")
      (node (ref "EXPANSION") (pin "9") (pinfunction "9_9") (pintype "passive"))
      (node (ref "STM32F303VE") (pin "16") (pinfunction "PC1_16") (pintype "bidirectional"))
    )
    (net (code "27") (name "/CT8") (class "Default")
      (node (ref "CF8") (pin "2") (pinfunction "2_2") (pintype "passive"))
      (node (ref "RF8") (pin "2") (pinfunction "2_2") (pintype "passive"))
      (node (ref "STM32F303VE") (pin "36") (pinfunction "PB1_36") (pintype "bidirectional"))
    )
    (net (code "28") (name "/CT9") (class "Default")
      (node (ref "CF9") (pin "2") (pinfunction "2_2") (pintype "passive"))
      (node (ref "RF9") (pin "2") (pinfunction "2_2") (pintype "passive"))
      (node (ref "STM32F303VE") (pin "35") (pinfunction "PB0_35") (pintype "bidirectional"))
    )
    (net (code "29") (name "/D+") (class "Default")
      (node (ref "R6") (pin "2") (pinfunction "2_2") (pintype "passive"))
      (node (ref "STM32F303VE") (pin "71") (pinfunction "PA12_71") (pintype "bidirectional"))
      (node (ref "TP5") (pin "TP") (pinfunction "TP_TP") (pintype "input"))
      (node (ref "USB-C") (pin "A6") (pinfunction "D1+_A6") (pintype "passive"))
    )
    (net (code "30") (name "/D-") (class "Default")
      (node (ref "STM32F303VE") (pin "70") (pinfunction "PA11_70") (pintype "bidirectional"))
      (node (ref "TP6") (pin "TP") (pinfunction "TP_TP") (pintype "input"))
      (node (ref "USB-C") (pin "A7") (pinfunction "D1-_A7") (pintype "passive"))
    )
    (net (code "31") (name "/DIO0") (class "Default")
      (node (ref "PCB2") (pin "P$58") (pinfunction "GPIO24_P$58") (pintype "bidirectional"))
      (node (ref "RFM69HCW") (pin "2") (pinfunction "~{IRQ}_2") (pintype "output"))
      (node (ref "STM32F303VE") (pin "89") (pinfunction "PB3_89") (pintype "bidirectional"))
      (node (ref "U1") (pin "24") (pinfunction "IO2_24") (pintype "bidirectional"))
    )
    (net (code "32") (name "/DS18B20_2_RJ45") (class "Default")
      (node (ref "R7") (pin "1") (pinfunction "1_1") (pintype "passive"))
      (node (ref "RJ45_2") (pin "4") (pinfunction "4_4") (pintype "bidirectional"))
      (node (ref "STM32F303VE") (pin "81") (pinfunction "PD0_81") (pintype "bidirectional"))
    )
    (net (code "33") (name "/DS18B20_RJ45") (class "Default")
      (node (ref "R1") (pin "1") (pinfunction "1_1") (pintype "passive"))
      (node (ref "RJ45_1") (pin "4") (pinfunction "4_4") (pintype "bidirectional"))
      (node (ref "STM32F303VE") (pin "66") (pinfunction "PC9_66") (pintype "bidirectional"))
    )
    (net (code "34") (name "/HSE_IN") (class "Default")
      (node (ref "C30") (pin "1") (pinfunction "1_1") (pintype "passive"))
      (node (ref "HSE") (pin "1") (pinfunction "1_1") (pintype "passive"))
      (node (ref "STM32F303VE") (pin "12") (pinfunction "PF0/OSC_IN_12") (pintype "bidirectional"))
    )
    (net (code "35") (name "/HSE_OUT") (class "Default")
      (node (ref "R21") (pin "1") (pinfunction "1_1") (pintype "passive"))
      (node (ref "STM32F303VE") (pin "13") (pinfunction "PF1/OSC_OUT_13") (pintype "bidirectional"))
    )
    (net (code "36") (name "/HSPICS0") (class "Default")
      (node (ref "SJ13") (pin "1") (pinfunction "1_1") (pintype "passive"))
      (node (ref "U1") (pin "23") (pinfunction "IO15_23") (pintype "bidirectional"))
    )
    (net (code "37") (name "/HSPID") (class "Default")
      (node (ref "SJ9") (pin "1") (pinfunction "1_1") (pintype "passive"))
      (node (ref "U1") (pin "16") (pinfunction "IO13_16") (pintype "bidirectional"))
    )
    (net (code "38") (name "/HSPIQ") (class "Default")
      (node (ref "SJ4") (pin "1") (pinfunction "1_1") (pintype "passive"))
      (node (ref "U1") (pin "14") (pinfunction "IO12_14") (pintype "bidirectional"))
    )
    (net (code "39") (name "/HSPI_CLK") (class "Default")
      (node (ref "SJ10") (pin "1") (pinfunction "1_1") (pintype "passive"))
      (node (ref "U1") (pin "13") (pinfunction "IO14_13") (pintype "bidirectional"))
    )
    (net (code "40") (name "/IO1_EX") (class "Default")
      (node (ref "EXPANSION") (pin "15") (pinfunction "15_15") (pintype "passive"))
      (node (ref "STM32F303VE") (pin "97") (pinfunction "PE0_97") (pintype "bidirectional"))
    )
    (net (code "41") (name "/IO2_EX") (class "Default")
      (node (ref "EXPANSION") (pin "16") (pinfunction "16_16") (pintype "passive"))
      (node (ref "STM32F303VE") (pin "98") (pinfunction "PE1_98") (pintype "bidirectional"))
    )
    (net (code "42") (name "/IO3_EX") (class "Default")
      (node (ref "EXPANSION") (pin "17") (pinfunction "17_17") (pintype "passive"))
      (node (ref "STM32F303VE") (pin "1") (pinfunction "PE2_1") (pintype "bidirectional"))
    )
    (net (code "43") (name "/IO4_EX") (class "Default")
      (node (ref "EXPANSION") (pin "18") (pinfunction "18_18") (pintype "passive"))
      (node (ref "STM32F303VE") (pin "2") (pinfunction "PE3_2") (pintype "bidirectional"))
    )
    (net (code "44") (name "/IO5_EX") (class "Default")
      (node (ref "EXPANSION") (pin "19") (pinfunction "19_19") (pintype "passive"))
      (node (ref "STM32F303VE") (pin "3") (pinfunction "PE4_3") (pintype "bidirectional"))
    )
    (net (code "45") (name "/IO6_EX") (class "Default")
      (node (ref "EXPANSION") (pin "21") (pinfunction "21_21") (pintype "passive"))
      (node (ref "STM32F303VE") (pin "4") (pinfunction "PE5_4") (pintype "bidirectional"))
    )
    (net (code "46") (name "/IO7_EX") (class "Default")
      (node (ref "EXPANSION") (pin "23") (pinfunction "23_23") (pintype "passive"))
      (node (ref "STM32F303VE") (pin "5") (pinfunction "PE6_5") (pintype "bidirectional"))
    )
    (net (code "47") (name "/IO8_EX") (class "Default")
      (node (ref "STM32F303VE") (pin "91") (pinfunction "PB5_91") (pintype "bidirectional"))
    )
    (net (code "48") (name "/IO11_EX") (class "Default")
      (node (ref "STM32F303VE") (pin "95") (pinfunction "PB8_95") (pintype "bidirectional"))
    )
    (net (code "49") (name "/LED1_GREEN") (class "Default")
      (node (ref "R3") (pin "2") (pinfunction "2_2") (pintype "passive"))
      (node (ref "STM32F303VE") (pin "55") (pinfunction "PD8_55") (pintype "bidirectional"))
    )
    (net (code "50") (name "/LED2_YELLOW") (class "Default")
      (node (ref "R4") (pin "2") (pinfunction "2_2") (pintype "passive"))
      (node (ref "STM32F303VE") (pin "56") (pinfunction "PD9_56") (pintype "bidirectional"))
    )
    (net (code "51") (name "/LED3_RED") (class "Default")
      (node (ref "R5") (pin "2") (pinfunction "2_2") (pintype "passive"))
      (node (ref "STM32F303VE") (pin "57") (pinfunction "PD10_57") (pintype "bidirectional"))
    )
    (net (code "52") (name "/MBUS_I{slash}O") (class "Default")
      (node (ref "Q1") (pin "2") (pinfunction "E_2") (pintype "passive"))
      (node (ref "R17") (pin "1") (pinfunction "1_1") (pintype "passive"))
      (node (ref "U$6") (pin "P$2") (pinfunction "P$2_P$2") (pintype "bidirectional"))
    )
    (net (code "53") (name "/MBUS_RX") (class "Default")
      (node (ref "R18") (pin "2") (pinfunction "2_2") (pintype "passive"))
      (node (ref "SJ11") (pin "2") (pinfunction "2_2") (pintype "passive"))
      (node (ref "SJ33") (pin "2") (pinfunction "2_2") (pintype "passive"))
    )
    (net (code "54") (name "/MBUS_TX") (class "Default")
      (node (ref "R19") (pin "2") (pinfunction "2_2") (pintype "passive"))
      (node (ref "SJ12") (pin "2") (pinfunction "2_2") (pintype "passive"))
      (node (ref "SJ31") (pin "2") (pinfunction "2_2") (pintype "passive"))
    )
    (net (code "55") (name "/MISO") (class "Default")
      (node (ref "RFM69HCW") (pin "1") (pinfunction "SDO_1") (pintype "output"))
      (node (ref "SJ16") (pin "2") (pinfunction "2_2") (pintype "passive"))
      (node (ref "SJ4") (pin "2") (pinfunction "2_2") (pintype "passive"))
      (node (ref "SJ6") (pin "1") (pinfunction "1_1") (pintype "passive"))
    )
    (net (code "56") (name "/MOSI") (class "Default")
      (node (ref "RFM69HCW") (pin "12") (pinfunction "SDI_12") (pintype "input"))
      (node (ref "SJ17") (pin "2") (pinfunction "2_2") (pintype "passive"))
      (node (ref "SJ5") (pin "1") (pinfunction "1_1") (pintype "passive"))
      (node (ref "SJ9") (pin "2") (pinfunction "2_2") (pintype "passive"))
    )
    (net (code "57") (name "/NRST_STM") (class "Default")
      (node (ref "S2") (pin "2") (pinfunction "2_2") (pintype "bidirectional"))
      (node (ref "SJ25") (pin "2") (pinfunction "2_2") (pintype "passive"))
      (node (ref "SJ32") (pin "1") (pinfunction "1_1") (pintype "passive"))
      (node (ref "STM32F303VE") (pin "14") (pinfunction "NRST_14") (pintype "bidirectional"))
      (node (ref "SV1") (pin "6") (pinfunction "6_6") (pintype "passive"))
    )
    (net (code "58") (name "/PC14") (class "Default")
      (node (ref "C31") (pin "1") (pinfunction "1_1") (pintype "passive"))
      (node (ref "LSE") (pin "P$1") (pinfunction "1_P$1") (pintype "passive"))
      (node (ref "STM32F303VE") (pin "8") (pinfunction "PC14/OSC32_IN_8") (pintype "bidirectional"))
    )
    (net (code "59") (name "/PC15") (class "Default")
      (node (ref "C32") (pin "1") (pinfunction "1_1") (pintype "passive"))
      (node (ref "LSE") (pin "P$4") (pinfunction "2_P$4") (pintype "passive"))
      (node (ref "STM32F303VE") (pin "9") (pinfunction "PC15/OSC32_OUT_9") (pintype "bidirectional"))
    )
    (net (code "60") (name "/PULSE1_RJ45") (class "Default")
      (node (ref "C41") (pin "1") (pinfunction "1_1") (pintype "passive"))
      (node (ref "RJ45_1") (pin "6") (pinfunction "6_6") (pintype "bidirectional"))
      (node (ref "STM32F303VE") (pin "67") (pinfunction "PA8_67") (pintype "bidirectional"))
    )
    (net (code "61") (name "/PULSE_2_RJ45") (class "Default")
      (node (ref "C46") (pin "1") (pinfunction "1_1") (pintype "passive"))
      (node (ref "RJ45_2") (pin "6") (pinfunction "6_6") (pintype "bidirectional"))
    )
    (net (code "62") (name "/PUSHIN_1") (class "Default")
      (node (ref "C1") (pin "1") (pinfunction "1_1") (pintype "passive"))
      (node (ref "D17") (pin "K") (pinfunction "C_K") (pintype "passive"))
      (node (ref "STM32F303VE") (pin "63") (pinfunction "PC6_63") (pintype "bidirectional"))
      (node (ref "U$1") (pin "P$2") (pinfunction "P$2_P$2") (pintype "bidirectional"))
    )
    (net (code "63") (name "/PUSHIN_2") (class "Default")
      (node (ref "C19") (pin "1") (pinfunction "1_1") (pintype "passive"))
      (node (ref "D18") (pin "K") (pinfunction "C_K") (pintype "passive"))
      (node (ref "STM32F303VE") (pin "64") (pinfunction "PC7_64") (pintype "bidirectional"))
      (node (ref "U$3") (pin "P$2") (pinfunction "P$2_P$2") (pintype "bidirectional"))
    )
    (net (code "64") (name "/PUSHIN_3") (class "Default")
      (node (ref "C20") (pin "1") (pinfunction "1_1") (pintype "passive"))
      (node (ref "D21") (pin "K") (pinfunction "C_K") (pintype "passive"))
      (node (ref "STM32F303VE") (pin "65") (pinfunction "PC8_65") (pintype "bidirectional"))
      (node (ref "U$4") (pin "P$2") (pinfunction "P$2_P$2") (pintype "bidirectional"))
    )
    (net (code "65") (name "/PUSHIN_BYANT") (class "Default")
      (node (ref "C22") (pin "1") (pinfunction "1_1") (pintype "passive"))
      (node (ref "D26") (pin "K") (pinfunction "C_K") (pintype "passive"))
      (node (ref "STM32F303VE") (pin "96") (pinfunction "PB9_96") (pintype "bidirectional"))
      (node (ref "U$5") (pin "P$2") (pinfunction "P$2_P$2") (pintype "bidirectional"))
    )
    (net (code "66") (name "/RPI_GPIO16") (class "Default")
      (node (ref "SJ29") (pin "2") (pinfunction "2_2") (pintype "passive"))
      (node (ref "STM32F303VE") (pin "59") (pinfunction "PD12_59") (pintype "bidirectional"))
    )
    (net (code "67") (name "/RPI_GPIO20") (class "Default")
      (node (ref "SJ30") (pin "2") (pinfunction "2_2") (pintype "passive"))
      (node (ref "STM32F303VE") (pin "60") (pinfunction "PD13_60") (pintype "bidirectional"))
    )
    (net (code "68") (name "/RPI_MISO") (class "Default")
      (node (ref "PCB2") (pin "P$61") (pinfunction "GPIO9_P$61") (pintype "bidirectional"))
      (node (ref "SJ6") (pin "2") (pinfunction "2_2") (pintype "passive"))
    )
    (net (code "69") (name "/RPI_MOSI") (class "Default")
      (node (ref "PCB2") (pin "P$59") (pinfunction "GPIO10_P$59") (pintype "bidirectional"))
      (node (ref "SJ5") (pin "2") (pinfunction "2_2") (pintype "passive"))
    )
    (net (code "70") (name "/RPI_SPI_CLK") (class "Default")
      (node (ref "PCB2") (pin "P$63") (pinfunction "GPIO11_P$63") (pintype "bidirectional"))
      (node (ref "SJ7") (pin "2") (pinfunction "2_2") (pintype "passive"))
    )
    (net (code "71") (name "/RST_RFM") (class "Default")
      (node (ref "RFM69HCW") (pin "6") (pinfunction "~{RES}_6") (pintype "bidirectional"))
      (node (ref "SJ24") (pin "2") (pinfunction "2_2") (pintype "passive"))
      (node (ref "SJ28") (pin "1") (pinfunction "1_1") (pintype "passive"))
    )
    (net (code "72") (name "/RXD0_ESP") (class "Default")
      (node (ref "SJ18") (pin "1") (pinfunction "1_1") (pintype "passive"))
      (node (ref "SJ21") (pin "2") (pinfunction "2_2") (pintype "passive"))
      (node (ref "SV2") (pin "4") (pinfunction "4_4") (pintype "passive"))
      (node (ref "U1") (pin "34") (pinfunction "RXD0_34") (pintype "bidirectional"))
    )
    (net (code "73") (name "/SCL") (class "Default")
      (node (ref "EXPANSION") (pin "22") (pinfunction "22_22") (pintype "passive"))
      (node (ref "OLED") (pin "2") (pinfunction "2_2") (pintype "passive"))
      (node (ref "R13") (pin "2") (pinfunction "2_2") (pintype "passive"))
      (node (ref "SJ27") (pin "2") (pinfunction "2_2") (pintype "passive"))
      (node (ref "STM32F303VE") (pin "92") (pinfunction "PB6_92") (pintype "bidirectional"))
      (node (ref "U1") (pin "36") (pinfunction "IO22_36") (pintype "bidirectional"))
    )
    (net (code "74") (name "/SDA") (class "Default")
      (node (ref "EXPANSION") (pin "20") (pinfunction "20_20") (pintype "passive"))
      (node (ref "OLED") (pin "1") (pinfunction "1_1") (pintype "passive"))
      (node (ref "R20") (pin "2") (pinfunction "2_2") (pintype "passive"))
      (node (ref "SJ26") (pin "1") (pinfunction "1_1") (pintype "passive"))
      (node (ref "STM32F303VE") (pin "93") (pinfunction "PB7_93") (pintype "bidirectional"))
      (node (ref "U1") (pin "33") (pinfunction "IO21_33") (pintype "bidirectional"))
    )
    (net (code "75") (name "/SPI3_CLK") (class "Default")
      (node (ref "SJ15") (pin "1") (pinfunction "1_1") (pintype "passive"))
      (node (ref "STM32F303VE") (pin "78") (pinfunction "PC10_78") (pintype "bidirectional"))
    )
    (net (code "76") (name "/SPI3_CS") (class "Default")
      (node (ref "SJ14") (pin "2") (pinfunction "2_2") (pintype "passive"))
      (node (ref "STM32F303VE") (pin "77") (pinfunction "PA15_77") (pintype "bidirectional"))
    )
    (net (code "77") (name "/SPI3_CS_ESP") (class "Default")
      (node (ref "STM32F303VE") (pin "84") (pinfunction "PD3_84") (pintype "bidirectional"))
    )
    (net (code "78") (name "/SPI3_MISO") (class "Default")
      (node (ref "SJ16") (pin "1") (pinfunction "1_1") (pintype "passive"))
      (node (ref "STM32F303VE") (pin "79") (pinfunction "PC11_79") (pintype "bidirectional"))
    )
    (net (code "79") (name "/SPI3_MOSI") (class "Default")
      (node (ref "SJ17") (pin "1") (pinfunction "1_1") (pintype "passive"))
      (node (ref "STM32F303VE") (pin "80") (pinfunction "PC12_80") (pintype "bidirectional"))
    )
    (net (code "80") (name "/SPI_CLK") (class "Default")
      (node (ref "RFM69HCW") (pin "13") (pinfunction "SCK_13") (pintype "input"))
      (node (ref "SJ10") (pin "2") (pinfunction "2_2") (pintype "passive"))
      (node (ref "SJ15") (pin "2") (pinfunction "2_2") (pintype "passive"))
      (node (ref "SJ7") (pin "1") (pinfunction "1_1") (pintype "passive"))
    )
    (net (code "81") (name "/SWCLK") (class "Default")
      (node (ref "STM32F303VE") (pin "76") (pinfunction "PA14_76") (pintype "bidirectional"))
      (node (ref "ST_LINK") (pin "1") (pinfunction "1_1") (pintype "passive"))
    )
    (net (code "82") (name "/SWDIO") (class "Default")
      (node (ref "STM32F303VE") (pin "72") (pinfunction "PA13_72") (pintype "bidirectional"))
      (node (ref "ST_LINK") (pin "2") (pinfunction "2_2") (pintype "passive"))
    )
    (net (code "83") (name "/TXD0_ESP") (class "Default")
      (node (ref "SJ20") (pin "2") (pinfunction "2_2") (pintype "passive"))
      (node (ref "SJ3") (pin "1") (pinfunction "1_1") (pintype "passive"))
      (node (ref "SV2") (pin "5") (pinfunction "5_5") (pintype "passive"))
      (node (ref "U1") (pin "35") (pinfunction "TXD0_35") (pintype "bidirectional"))
    )
    (net (code "84") (name "/UART1_RX") (class "Default")
      (node (ref "PCB2") (pin "P$48") (pinfunction "GPIO14_P$48") (pintype "bidirectional"))
      (node (ref "SJ11") (pin "1") (pinfunction "1_1") (pintype "passive"))
      (node (ref "SJ20") (pin "1") (pinfunction "1_1") (pintype "passive"))
      (node (ref "STM32F303VE") (pin "69") (pinfunction "PA10_69") (pintype "bidirectional"))
      (node (ref "UART1") (pin "1") (pinfunction "1_1") (pintype "passive"))
    )
    (net (code "85") (name "/UART1_TX") (class "Default")
      (node (ref "PCB2") (pin "P$50") (pinfunction "GPIO15_P$50") (pintype "bidirectional"))
      (node (ref "SJ12") (pin "1") (pinfunction "1_1") (pintype "passive"))
      (node (ref "SJ21") (pin "1") (pinfunction "1_1") (pintype "passive"))
      (node (ref "STM32F303VE") (pin "68") (pinfunction "PA9_68") (pintype "bidirectional"))
      (node (ref "UART1") (pin "2") (pinfunction "2_2") (pintype "passive"))
    )
    (net (code "86") (name "/UART2_RX") (class "Default")
      (node (ref "STM32F303VE") (pin "26") (pinfunction "PA3_26") (pintype "bidirectional"))
      (node (ref "SV1") (pin "4") (pinfunction "4_4") (pintype "passive"))
    )
    (net (code "87") (name "/UART2_TX") (class "Default")
      (node (ref "STM32F303VE") (pin "25") (pinfunction "PA2_25") (pintype "bidirectional"))
      (node (ref "STM32F303VE") (pin "86") (pinfunction "PD5_86") (pintype "bidirectional"))
      (node (ref "SV1") (pin "5") (pinfunction "5_5") (pintype "passive"))
    )
    (net (code "88") (name "/USART3_RX") (class "Default")
      (node (ref "SJ3") (pin "2") (pinfunction "2_2") (pintype "passive"))
      (node (ref "STM32F303VE") (pin "48") (pinfunction "PB11_48") (pintype "bidirectional"))
    )
    (net (code "89") (name "/USART3_TX") (class "Default")
      (node (ref "SJ18") (pin "2") (pinfunction "2_2") (pintype "passive"))
      (node (ref "STM32F303VE") (pin "47") (pinfunction "PB10_47") (pintype "bidirectional"))
    )
    (net (code "90") (name "/VBAT") (class "Default")
      (node (ref "G1") (pin "+") (pinfunction "+_+") (pintype "passive"))
      (node (ref "R8") (pin "2") (pinfunction "2_2") (pintype "passive"))
      (node (ref "STM32F303VE") (pin "6") (pinfunction "VBAT_6") (pintype "bidirectional"))
    )
    (net (code "91") (name "/VREF+") (class "Default")
      (node (ref "C23") (pin "1") (pinfunction "1_1") (pintype "passive"))
      (node (ref "JP1") (pin "3") (pinfunction "3_3") (pintype "passive"))
      (node (ref "SJ2") (pin "2") (pinfunction "2_2") (pintype "passive"))
      (node (ref "STM32F303VE") (pin "21") (pinfunction "VREF+_21") (pintype "bidirectional"))
      (node (ref "VREF_3V3") (pin "1") (pinfunction "OUT_1") (pintype "bidirectional"))
    )
    (net (code "92") (name "/VSIG1") (class "Default")
      (node (ref "CV1") (pin "1") (pinfunction "1_1") (pintype "passive"))
      (node (ref "D2") (pin "K") (pinfunction "C_K") (pintype "passive"))
      (node (ref "RV1") (pin "2") (pinfunction "2_2") (pintype "passive"))
      (node (ref "STM32F303VE") (pin "23") (pinfunction "PA0_23") (pintype "bidirectional"))
    )
    (net (code "93") (name "/VSIG2") (class "Default")
      (node (ref "CV2") (pin "1") (pinfunction "1_1") (pintype "passive"))
      (node (ref "D3") (pin "K") (pinfunction "C_K") (pintype "passive"))
      (node (ref "RV2") (pin "2") (pinfunction "2_2") (pintype "passive"))
      (node (ref "STM32F303VE") (pin "24") (pinfunction "PA1_24") (pintype "bidirectional"))
    )
    (net (code "94") (name "/VSIG3") (class "Default")
      (node (ref "CV3") (pin "1") (pinfunction "1_1") (pintype "passive"))
      (node (ref "D4") (pin "K") (pinfunction "C_K") (pintype "passive"))
      (node (ref "RV3") (pin "2") (pinfunction "2_2") (pintype "passive"))
      (node (ref "STM32F303VE") (pin "27") (pinfunction "PF4_27") (pintype "bidirectional"))
    )
    (net (code "95") (name "/VSIG4") (class "Default")
      (node (ref "EXPANSION") (pin "11") (pinfunction "11_11") (pintype "passive"))
      (node (ref "STM32F303VE") (pin "17") (pinfunction "PC2_17") (pintype "bidirectional"))
    )
    (net (code "96") (name "/VSIG5") (class "Default")
      (node (ref "EXPANSION") (pin "12") (pinfunction "12_12") (pintype "passive"))
      (node (ref "STM32F303VE") (pin "18") (pinfunction "PC3_18") (pintype "bidirectional"))
    )
    (net (code "97") (name "/VSIG6") (class "Default")
      (node (ref "EXPANSION") (pin "13") (pinfunction "13_13") (pintype "passive"))
      (node (ref "STM32F303VE") (pin "19") (pinfunction "PF2_19") (pintype "bidirectional"))
    )
    (net (code "98") (name "GND") (class "Default")
      (node (ref "BOOT_ESP") (pin "1") (pinfunction "1_1") (pintype "passive"))
      (node (ref "C1") (pin "2") (pinfunction "2_2") (pintype "passive"))
      (node (ref "C10") (pin "2") (pinfunction "2_2") (pintype "passive"))
      (node (ref "C11") (pin "2") (pinfunction "2_2") (pintype "passive"))
      (node (ref "C12") (pin "1") (pinfunction "1_1") (pintype "passive"))
      (node (ref "C13") (pin "2") (pinfunction "2_2") (pintype "passive"))
      (node (ref "C14") (pin "2") (pinfunction "2_2") (pintype "passive"))
      (node (ref "C15") (pin "1") (pinfunction "1_1") (pintype "passive"))
      (node (ref "C17") (pin "2") (pinfunction "2_2") (pintype "passive"))
      (node (ref "C18") (pin "2") (pinfunction "2_2") (pintype "passive"))
      (node (ref "C19") (pin "2") (pinfunction "2_2") (pintype "passive"))
      (node (ref "C2") (pin "2") (pinfunction "2_2") (pintype "passive"))
      (node (ref "C20") (pin "2") (pinfunction "2_2") (pintype "passive"))
      (node (ref "C21") (pin "2") (pinfunction "2_2") (pintype "passive"))
      (node (ref "C22") (pin "2") (pinfunction "2_2") (pintype "passive"))
      (node (ref "C23") (pin "2") (pinfunction "2_2") (pintype "passive"))
      (node (ref "C24") (pin "2") (pinfunction "2_2") (pintype "passive"))
      (node (ref "C25") (pin "2") (pinfunction "2_2") (pintype "passive"))
      (node (ref "C26") (pin "2") (pinfunction "2_2") (pintype "passive"))
      (node (ref "C27") (pin "2") (pinfunction "2_2") (pintype "passive"))
      (node (ref "C28") (pin "2") (pinfunction "2_2") (pintype "passive"))
      (node (ref "C29") (pin "2") (pinfunction "2_2") (pintype "passive"))
      (node (ref "C3") (pin "2") (pinfunction "2_2") (pintype "passive"))
      (node (ref "C30") (pin "2") (pinfunction "2_2") (pintype "passive"))
      (node (ref "C31") (pin "2") (pinfunction "2_2") (pintype "passive"))
      (node (ref "C32") (pin "2") (pinfunction "2_2") (pintype "passive"))
      (node (ref "C4") (pin "1") (pinfunction "1_1") (pintype "passive"))
      (node (ref "C40") (pin "2") (pinfunction "2_2") (pintype "passive"))
      (node (ref "C41") (pin "2") (pinfunction "2_2") (pintype "passive"))
      (node (ref "C42") (pin "2") (pinfunction "2_2") (pintype "passive"))
      (node (ref "C45") (pin "2") (pinfunction "2_2") (pintype "passive"))
      (node (ref "C46") (pin "2") (pinfunction "2_2") (pintype "passive"))
      (node (ref "C47") (pin "2") (pinfunction "2_2") (pintype "passive"))
      (node (ref "C5") (pin "1") (pinfunction "1_1") (pintype "passive"))
      (node (ref "C50*") (pin "1") (pinfunction "1_1") (pintype "passive"))
      (node (ref "C6") (pin "1") (pinfunction "1_1") (pintype "passive"))
      (node (ref "C7") (pin "2") (pinfunction "2_2") (pintype "passive"))
      (node (ref "C8") (pin "1") (pinfunction "1_1") (pintype "passive"))
      (node (ref "C9") (pin "1") (pinfunction "1_1") (pintype "passive"))
      (node (ref "CF1") (pin "1") (pinfunction "1_1") (pintype "passive"))
      (node (ref "CF2") (pin "1") (pinfunction "1_1") (pintype "passive"))
      (node (ref "CF3") (pin "1") (pinfunction "1_1") (pintype "passive"))
      (node (ref "CF4") (pin "1") (pinfunction "1_1") (pintype "passive"))
      (node (ref "CF5") (pin "1") (pinfunction "1_1") (pintype "passive"))
      (node (ref "CF6") (pin "1") (pinfunction "1_1") (pintype "passive"))
      (node (ref "CF7") (pin "1") (pinfunction "1_1") (pintype "passive"))
      (node (ref "CF8") (pin "1") (pinfunction "1_1") (pintype "passive"))
      (node (ref "CF9") (pin "1") (pinfunction "1_1") (pintype "passive"))
      (node (ref "CV1") (pin "2") (pinfunction "2_2") (pintype "passive"))
      (node (ref "CV2") (pin "2") (pinfunction "2_2") (pintype "passive"))
      (node (ref "CV3") (pin "2") (pinfunction "2_2") (pintype "passive"))
      (node (ref "D1") (pin "A") (pinfunction "A_A") (pintype "passive"))
      (node (ref "D10") (pin "A") (pinfunction "A_A") (pintype "passive"))
      (node (ref "D11") (pin "A") (pinfunction "A_A") (pintype "passive"))
      (node (ref "D12") (pin "A") (pinfunction "A_A") (pintype "passive"))
      (node (ref "D13") (pin "A") (pinfunction "A_A") (pintype "passive"))
      (node (ref "D17") (pin "A") (pinfunction "A_A") (pintype "passive"))
      (node (ref "D18") (pin "A") (pinfunction "A_A") (pintype "passive"))
      (node (ref "D2") (pin "A") (pinfunction "A_A") (pintype "passive"))
      (node (ref "D21") (pin "A") (pinfunction "A_A") (pintype "passive"))
      (node (ref "D22") (pin "A") (pinfunction "A_A") (pintype "passive"))
      (node (ref "D23") (pin "A") (pinfunction "A_A") (pintype "passive"))
      (node (ref "D26") (pin "A") (pinfunction "A_A") (pintype "passive"))
      (node (ref "D3") (pin "A") (pinfunction "A_A") (pintype "passive"))
      (node (ref "D4") (pin "A") (pinfunction "A_A") (pintype "passive"))
      (node (ref "D40*1") (pin "A") (pinfunction "A_A") (pintype "passive"))
      (node (ref "D5") (pin "A") (pinfunction "A_A") (pintype "passive"))
      (node (ref "D6") (pin "A") (pinfunction "A_A") (pintype "passive"))
      (node (ref "D7") (pin "A") (pinfunction "A_A") (pintype "passive"))
      (node (ref "D8") (pin "A") (pinfunction "A_A") (pintype "passive"))
      (node (ref "D9") (pin "A") (pinfunction "A_A") (pintype "passive"))
      (node (ref "EXPANSION") (pin "1") (pinfunction "1_1") (pintype "passive"))
      (node (ref "EXPANSION") (pin "14") (pinfunction "14_14") (pintype "passive"))
      (node (ref "EXPANSION") (pin "2") (pinfunction "2_2") (pintype "passive"))
      (node (ref "EXPANSION") (pin "25") (pinfunction "25_25") (pintype "passive"))
      (node (ref "G1") (pin "-") (pinfunction "-_-") (pintype "passive"))
      (node (ref "J$1") (pin "GND@0") (pinfunction "GND_GND@0") (pintype "bidirectional"))
      (node (ref "J$1") (pin "GND@1") (pinfunction "GND_GND@1") (pintype "bidirectional"))
      (node (ref "J$1") (pin "GND@2") (pinfunction "GND_GND@2") (pintype "bidirectional"))
      (node (ref "J$1") (pin "GND@3") (pinfunction "GND_GND@3") (pintype "bidirectional"))
      (node (ref "LED1") (pin "C") (pinfunction "C_C") (pintype "passive"))
      (node (ref "LED2") (pin "C") (pinfunction "C_C") (pintype "passive"))
      (node (ref "LED3") (pin "C") (pinfunction "C_C") (pintype "passive"))
      (node (ref "LED4") (pin "C") (pinfunction "C_C") (pintype "passive"))
      (node (ref "MCP1825") (pin "2") (pinfunction "GND_2") (pintype "power_in"))
      (node (ref "MCP1825") (pin "4") (pinfunction "GND_4") (pintype "power_in"))
      (node (ref "OLED") (pin "4") (pinfunction "4_4") (pintype "passive"))
      (node (ref "PCB2") (pin "P$46") (pinfunction "GND_P$46") (pintype "bidirectional"))
      (node (ref "PCB2") (pin "P$49") (pinfunction "GND_P$49") (pintype "bidirectional"))
      (node (ref "PCB2") (pin "P$54") (pinfunction "GND_P$54") (pintype "bidirectional"))
      (node (ref "PCB2") (pin "P$60") (pinfunction "GND_P$60") (pintype "bidirectional"))
      (node (ref "PCB2") (pin "P$65") (pinfunction "GND_P$65") (pintype "bidirectional"))
      (node (ref "PCB2") (pin "P$70") (pinfunction "GND_P$70") (pintype "bidirectional"))
      (node (ref "PCB2") (pin "P$74") (pinfunction "GND_P$74") (pintype "bidirectional"))
      (node (ref "PCB2") (pin "P$79") (pinfunction "GND_P$79") (pintype "bidirectional"))
      (node (ref "Q2") (pin "2") (pinfunction "E_2") (pintype "passive"))
      (node (ref "Q3") (pin "2") (pinfunction "E_2") (pintype "passive"))
      (node (ref "Q4") (pin "1") (pinfunction "G_1") (pintype "passive"))
      (node (ref "R14") (pin "1") (pinfunction "1_1") (pintype "passive"))
      (node (ref "R15") (pin "1") (pinfunction "1_1") (pintype "passive"))
      (node (ref "R16") (pin "1") (pinfunction "1_1") (pintype "passive"))
      (node (ref "R2") (pin "2") (pinfunction "2_2") (pintype "passive"))
      (node (ref "R23") (pin "1") (pinfunction "1_1") (pintype "passive"))
      (node (ref "RFM69HCW") (pin "10") (pinfunction "GND_10") (pintype "passive"))
      (node (ref "RFM69HCW") (pin "7") (pinfunction "GND_7") (pintype "passive"))
      (node (ref "RJ45_1") (pin "1") (pinfunction "1_1") (pintype "bidirectional"))
      (node (ref "RJ45_1") (pin "3") (pinfunction "3_3") (pintype "bidirectional"))
      (node (ref "RJ45_1") (pin "5") (pinfunction "5_5") (pintype "bidirectional"))
      (node (ref "RJ45_2") (pin "1") (pinfunction "1_1") (pintype "bidirectional"))
      (node (ref "RJ45_2") (pin "3") (pinfunction "3_3") (pintype "bidirectional"))
      (node (ref "RJ45_2") (pin "5") (pinfunction "5_5") (pintype "bidirectional"))
      (node (ref "S1") (pin "1") (pinfunction "1_1") (pintype "bidirectional"))
      (node (ref "S2") (pin "1") (pinfunction "1_1") (pintype "bidirectional"))
      (node (ref "STM32F303VE") (pin "20") (pinfunction "VSSA/VREF-_20") (pintype "bidirectional"))
      (node (ref "STM32F303VE") (pin "49") (pinfunction "VSS_49") (pintype "bidirectional"))
      (node (ref "STM32F303VE") (pin "74") (pinfunction "VSS_74") (pintype "bidirectional"))
      (node (ref "STM32F303VE") (pin "99") (pinfunction "VSS_99") (pintype "bidirectional"))
      (node (ref "SV1") (pin "1") (pinfunction "1_1") (pintype "passive"))
      (node (ref "SV2") (pin "1") (pinfunction "1_1") (pintype "passive"))
      (node (ref "U$1") (pin "P$3") (pinfunction "P$1_P$3") (pintype "bidirectional"))
      (node (ref "U$2") (pin "P$1") (pinfunction "GND_P$1") (pintype "bidirectional"))
      (node (ref "U$2") (pin "P$2") (pinfunction "GND._P$2") (pintype "bidirectional"))
      (node (ref "U$3") (pin "P$3") (pinfunction "P$1_P$3") (pintype "bidirectional"))
      (node (ref "U$4") (pin "P$3") (pinfunction "P$1_P$3") (pintype "bidirectional"))
      (node (ref "U$5") (pin "P$3") (pinfunction "P$1_P$3") (pintype "bidirectional"))
      (node (ref "U$6") (pin "P$3") (pinfunction "P$1_P$3") (pintype "bidirectional"))
      (node (ref "U1") (pin "1") (pinfunction "GND_1") (pintype "power_in"))
      (node (ref "U1") (pin "15") (pinfunction "GND_15") (pintype "power_in"))
      (node (ref "U1") (pin "31") (pinfunction "IO19_31") (pintype "bidirectional"))
      (node (ref "U1") (pin "38") (pinfunction "GND_38") (pintype "power_in"))
      (node (ref "U1") (pin "39") (pinfunction "GND_39") (pintype "power_in"))
      (node (ref "USB-C") (pin "A1/B12") (pinfunction "GND1_A1/B12") (pintype "passive"))
      (node (ref "USB-C") (pin "B1/A12") (pinfunction "GND2_B1/A12") (pintype "passive"))
      (node (ref "USB-C") (pin "GND1") (pinfunction "SHIELD_GND1") (pintype "bidirectional"))
      (node (ref "USB-C") (pin "GND2") (pinfunction "SHIELD_GND2") (pintype "bidirectional"))
      (node (ref "USB-C") (pin "GND3") (pinfunction "SHIELD_GND3") (pintype "bidirectional"))
      (node (ref "USB-C") (pin "GND4") (pinfunction "SHIELD_GND4") (pintype "bidirectional"))
      (node (ref "VREF_3V3") (pin "2") (pinfunction "GND_2") (pintype "bidirectional"))
      (node (ref "VREF_3V3") (pin "3") (pinfunction "GND_3") (pintype "bidirectional"))
      (node (ref "VREF_3V3") (pin "5") (pinfunction "GND_5") (pintype "bidirectional"))
    )
    (net (code "99") (name "Net-(C16-Pad1)") (class "Default")
      (node (ref "C16") (pin "1") (pinfunction "1_1") (pintype "passive"))
      (node (ref "SV2") (pin "6") (pinfunction "6_6") (pintype "passive"))
    )
    (net (code "100") (name "Net-(CT1-2)") (class "Default")
      (node (ref "CT1") (pin "P$2") (pinfunction "2_P$2") (pintype "bidirectional"))
      (node (ref "D13") (pin "K") (pinfunction "C_K") (pintype "passive"))
      (node (ref "RB18") (pin "1") (pinfunction "1_1") (pintype "passive"))
      (node (ref "RB9") (pin "1") (pinfunction "1_1") (pintype "passive"))
      (node (ref "RF9") (pin "1") (pinfunction "1_1") (pintype "passive"))
    )
    (net (code "101") (name "Net-(CT2-2)") (class "Default")
      (node (ref "CT2") (pin "P$2") (pinfunction "2_P$2") (pintype "bidirectional"))
      (node (ref "D12") (pin "K") (pinfunction "C_K") (pintype "passive"))
      (node (ref "RB17") (pin "1") (pinfunction "1_1") (pintype "passive"))
      (node (ref "RB8") (pin "1") (pinfunction "1_1") (pintype "passive"))
      (node (ref "RF8") (pin "1") (pinfunction "1_1") (pintype "passive"))
    )
    (net (code "102") (name "Net-(CT3-2)") (class "Default")
      (node (ref "CT3") (pin "P$2") (pinfunction "2_P$2") (pintype "bidirectional"))
      (node (ref "D11") (pin "K") (pinfunction "C_K") (pintype "passive"))
      (node (ref "RB16") (pin "1") (pinfunction "1_1") (pintype "passive"))
      (node (ref "RB7") (pin "1") (pinfunction "1_1") (pintype "passive"))
      (node (ref "RF7") (pin "1") (pinfunction "1_1") (pintype "passive"))
    )
    (net (code "103") (name "Net-(CT4-2)") (class "Default")
      (node (ref "CT4") (pin "P$2") (pinfunction "2_P$2") (pintype "bidirectional"))
      (node (ref "D10") (pin "K") (pinfunction "C_K") (pintype "passive"))
      (node (ref "RB13") (pin "1") (pinfunction "1_1") (pintype "passive"))
      (node (ref "RB6") (pin "1") (pinfunction "1_1") (pintype "passive"))
      (node (ref "RF6") (pin "1") (pinfunction "1_1") (pintype "passive"))
    )
    (net (code "104") (name "Net-(CT5-2)") (class "Default")
      (node (ref "CT5") (pin "P$2") (pinfunction "2_P$2") (pintype "bidirectional"))
      (node (ref "D9") (pin "K") (pinfunction "C_K") (pintype "passive"))
      (node (ref "RB14") (pin "1") (pinfunction "1_1") (pintype "passive"))
      (node (ref "RB5") (pin "1") (pinfunction "1_1") (pintype "passive"))
      (node (ref "RF5") (pin "1") (pinfunction "1_1") (pintype "passive"))
    )
    (net (code "105") (name "Net-(CT6-2)") (class "Default")
      (node (ref "CT6") (pin "P$2") (pinfunction "2_P$2") (pintype "bidirectional"))
      (node (ref "D8") (pin "K") (pinfunction "C_K") (pintype "passive"))
      (node (ref "RB15") (pin "1") (pinfunction "1_1") (pintype "passive"))
      (node (ref "RB4") (pin "1") (pinfunction "1_1") (pintype "passive"))
      (node (ref "RF4") (pin "1") (pinfunction "1_1") (pintype "passive"))
    )
    (net (code "106") (name "Net-(CT7-2)") (class "Default")
      (node (ref "CT7") (pin "P$2") (pinfunction "2_P$2") (pintype "bidirectional"))
      (node (ref "D7") (pin "K") (pinfunction "C_K") (pintype "passive"))
      (node (ref "RB12") (pin "1") (pinfunction "1_1") (pintype "passive"))
      (node (ref "RB3") (pin "1") (pinfunction "1_1") (pintype "passive"))
      (node (ref "RF3") (pin "1") (pinfunction "1_1") (pintype "passive"))
    )
    (net (code "107") (name "Net-(CT8-2)") (class "Default")
      (node (ref "CT8") (pin "P$2") (pinfunction "2_P$2") (pintype "bidirectional"))
      (node (ref "D6") (pin "K") (pinfunction "C_K") (pintype "passive"))
      (node (ref "RB11") (pin "1") (pinfunction "1_1") (pintype "passive"))
      (node (ref "RB2") (pin "1") (pinfunction "1_1") (pintype "passive"))
      (node (ref "RF2") (pin "1") (pinfunction "1_1") (pintype "passive"))
    )
    (net (code "108") (name "Net-(CT9-2)") (class "Default")
      (node (ref "CT9") (pin "P$2") (pinfunction "2_P$2") (pintype "bidirectional"))
      (node (ref "D5") (pin "K") (pinfunction "C_K") (pintype "passive"))
      (node (ref "RB1") (pin "1") (pinfunction "1_1") (pintype "passive"))
      (node (ref "RB10") (pin "1") (pinfunction "1_1") (pintype "passive"))
      (node (ref "RF1") (pin "1") (pinfunction "1_1") (pintype "passive"))
    )
    (net (code "109") (name "Net-(HSE-2)") (class "Default")
      (node (ref "C29") (pin "1") (pinfunction "1_1") (pintype "passive"))
      (node (ref "HSE") (pin "3") (pinfunction "2_3") (pintype "passive"))
      (node (ref "R21") (pin "2") (pinfunction "2_2") (pintype "passive"))
    )
    (net (code "110") (name "Net-(J$1-SIGNAL)") (class "Default")
      (node (ref "J$1") (pin "SIG") (pinfunction "SIGNAL_SIG") (pintype "bidirectional"))
      (node (ref "RFM69HCW") (pin "8") (pinfunction "ANT_8") (pintype "bidirectional"))
    )
    (net (code "111") (name "Net-(JP1-Pad2)") (class "Default")
      (node (ref "JP1") (pin "2") (pinfunction "2_2") (pintype "passive"))
      (node (ref "R22") (pin "2") (pinfunction "2_2") (pintype "passive"))
    )
    (net (code "112") (name "Net-(LED1-PadA)") (class "Default")
      (node (ref "LED1") (pin "A") (pinfunction "A_A") (pintype "passive"))
      (node (ref "R3") (pin "1") (pinfunction "1_1") (pintype "passive"))
    )
    (net (code "113") (name "Net-(LED2-PadA)") (class "Default")
      (node (ref "LED2") (pin "A") (pinfunction "A_A") (pintype "passive"))
      (node (ref "R4") (pin "1") (pinfunction "1_1") (pintype "passive"))
    )
    (net (code "114") (name "Net-(LED3-PadA)") (class "Default")
      (node (ref "LED3") (pin "A") (pinfunction "A_A") (pintype "passive"))
      (node (ref "R5") (pin "1") (pinfunction "1_1") (pintype "passive"))
    )
    (net (code "115") (name "Net-(LED4-PadA)") (class "Default")
      (node (ref "LED4") (pin "A") (pinfunction "A_A") (pintype "passive"))
      (node (ref "R10") (pin "1") (pinfunction "1_1") (pintype "passive"))
    )
    (net (code "116") (name "Net-(PCB2-GPIO4)") (class "Default")
      (node (ref "J1") (pin "2") (pinfunction "2_2") (pintype "passive"))
      (node (ref "PCB2") (pin "P$47") (pinfunction "GPIO4_P$47") (pintype "bidirectional"))
    )
    (net (code "117") (name "Net-(PCB2-GPIO5)") (class "Default")
      (node (ref "PCB2") (pin "P$69") (pinfunction "GPIO5_P$69") (pintype "bidirectional"))
      (node (ref "SJ28") (pin "2") (pinfunction "2_2") (pintype "passive"))
    )
    (net (code "118") (name "Net-(PCB2-GPIO12)") (class "Default")
      (node (ref "PCB2") (pin "P$72") (pinfunction "GPIO12_P$72") (pintype "bidirectional"))
      (node (ref "SJ8") (pin "1") (pinfunction "1_1") (pintype "passive"))
    )
    (net (code "119") (name "Net-(PCB2-GPIO16)") (class "Default")
      (node (ref "PCB2") (pin "P$76") (pinfunction "GPIO16_P$76") (pintype "bidirectional"))
      (node (ref "SJ29") (pin "1") (pinfunction "1_1") (pintype "passive"))
    )
    (net (code "120") (name "Net-(PCB2-GPIO17)") (class "Default")
      (node (ref "PCB2") (pin "P$51") (pinfunction "GPIO17_P$51") (pintype "bidirectional"))
      (node (ref "SJ32") (pin "2") (pinfunction "2_2") (pintype "passive"))
    )
    (net (code "121") (name "Net-(PCB2-GPIO18)") (class "Default")
      (node (ref "PCB2") (pin "P$52") (pinfunction "GPIO18_P$52") (pintype "bidirectional"))
      (node (ref "SJ31") (pin "1") (pinfunction "1_1") (pintype "passive"))
    )
    (net (code "122") (name "Net-(PCB2-GPIO20)") (class "Default")
      (node (ref "PCB2") (pin "P$78") (pinfunction "GPIO20_P$78") (pintype "bidirectional"))
      (node (ref "SJ30") (pin "1") (pinfunction "1_1") (pintype "passive"))
    )
    (net (code "123") (name "Net-(PCB2-GPIO23)") (class "Default")
      (node (ref "PCB2") (pin "P$56") (pinfunction "GPIO23_P$56") (pintype "bidirectional"))
      (node (ref "SJ33") (pin "1") (pinfunction "1_1") (pintype "passive"))
    )
    (net (code "124") (name "Net-(PCB2-ID_SC*)") (class "Default")
      (node (ref "PCB2") (pin "P$68") (pinfunction "ID_SC*_P$68") (pintype "bidirectional"))
      (node (ref "SJ27") (pin "1") (pinfunction "1_1") (pintype "passive"))
    )
    (net (code "125") (name "Net-(PCB2-ID_SD*)") (class "Default")
      (node (ref "PCB2") (pin "P$67") (pinfunction "ID_SD*_P$67") (pintype "bidirectional"))
      (node (ref "SJ26") (pin "2") (pinfunction "2_2") (pintype "passive"))
    )
    (net (code "126") (name "Net-(Q1-B)") (class "Default")
      (node (ref "Q1") (pin "1") (pinfunction "B_1") (pintype "passive"))
      (node (ref "Q3") (pin "3") (pinfunction "C_3") (pintype "passive"))
      (node (ref "R14") (pin "2") (pinfunction "2_2") (pintype "passive"))
      (node (ref "R9") (pin "1") (pinfunction "1_1") (pintype "passive"))
    )
    (net (code "127") (name "Net-(Q1-C)") (class "Default")
      (node (ref "Q1") (pin "3") (pinfunction "C_3") (pintype "passive"))
      (node (ref "Q2") (pin "1") (pinfunction "B_1") (pintype "passive"))
      (node (ref "R16") (pin "2") (pinfunction "2_2") (pintype "passive"))
    )
    (net (code "128") (name "Net-(Q2-C)") (class "Default")
      (node (ref "Q2") (pin "3") (pinfunction "C_3") (pintype "passive"))
      (node (ref "R11") (pin "1") (pinfunction "1_1") (pintype "passive"))
      (node (ref "R15") (pin "2") (pinfunction "2_2") (pintype "passive"))
      (node (ref "R19") (pin "1") (pinfunction "1_1") (pintype "passive"))
    )
    (net (code "129") (name "Net-(Q3-B)") (class "Default")
      (node (ref "Q3") (pin "1") (pinfunction "B_1") (pintype "passive"))
      (node (ref "R18") (pin "1") (pinfunction "1_1") (pintype "passive"))
    )
    (net (code "130") (name "Net-(Q4-S)") (class "Default")
      (node (ref "Q4") (pin "2") (pinfunction "S_2") (pintype "passive"))
      (node (ref "R8") (pin "1") (pinfunction "1_1") (pintype "passive"))
    )
    (net (code "131") (name "Net-(R41-Pad2)") (class "Default")
      (node (ref "R41") (pin "2") (pinfunction "2_2") (pintype "passive"))
      (node (ref "R51") (pin "1") (pinfunction "1_1") (pintype "passive"))
      (node (ref "RV3") (pin "1") (pinfunction "1_1") (pintype "passive"))
    )
    (net (code "132") (name "Net-(R42-Pad1)") (class "Default")
      (node (ref "R42") (pin "1") (pinfunction "1_1") (pintype "passive"))
      (node (ref "R52") (pin "1") (pinfunction "1_1") (pintype "passive"))
      (node (ref "RV2") (pin "1") (pinfunction "1_1") (pintype "passive"))
    )
    (net (code "133") (name "Net-(R43-Pad1)") (class "Default")
      (node (ref "R43") (pin "1") (pinfunction "1_1") (pintype "passive"))
      (node (ref "R53") (pin "1") (pinfunction "1_1") (pintype "passive"))
      (node (ref "RV1") (pin "1") (pinfunction "1_1") (pintype "passive"))
    )
    (net (code "134") (name "Net-(RB16-Pad2)") (class "Default")
      (node (ref "RB16") (pin "2") (pinfunction "2_2") (pintype "passive"))
      (node (ref "RB7") (pin "2") (pinfunction "2_2") (pintype "passive"))
      (node (ref "S33") (pin "1") (pinfunction "1_1") (pintype "passive"))
    )
    (net (code "135") (name "Net-(RB17-Pad2)") (class "Default")
      (node (ref "RB17") (pin "2") (pinfunction "2_2") (pintype "passive"))
      (node (ref "RB8") (pin "2") (pinfunction "2_2") (pintype "passive"))
      (node (ref "S22") (pin "1") (pinfunction "1_1") (pintype "passive"))
    )
    (net (code "136") (name "Net-(RB18-Pad2)") (class "Default")
      (node (ref "RB18") (pin "2") (pinfunction "2_2") (pintype "passive"))
      (node (ref "RB9") (pin "2") (pinfunction "2_2") (pintype "passive"))
      (node (ref "S11") (pin "1") (pinfunction "1_1") (pintype "passive"))
    )
    (net (code "137") (name "Net-(SJ1-Pad1)") (class "Default")
      (node (ref "SJ1") (pin "1") (pinfunction "1_1") (pintype "passive"))
      (node (ref "SV1") (pin "2") (pinfunction "2_2") (pintype "passive"))
    )
    (net (code "138") (name "Net-(U1-3V3)") (class "Default")
      (node (ref "SJ23") (pin "1") (pinfunction "1_1") (pintype "passive"))
      (node (ref "U1") (pin "2") (pinfunction "3V3_2") (pintype "power_in"))
    )
    (net (code "139") (name "Net-(U1-EN)") (class "Default")
      (node (ref "C16") (pin "2") (pinfunction "2_2") (pintype "passive"))
      (node (ref "U1") (pin "3") (pinfunction "EN_3") (pintype "input"))
    )
    (net (code "140") (name "Net-(U1-IO0)") (class "Default")
      (node (ref "BOOT_ESP") (pin "2") (pinfunction "2_2") (pintype "passive"))
      (node (ref "U1") (pin "25") (pinfunction "IO0_25") (pintype "bidirectional"))
    )
    (net (code "141") (name "Net-(U1-IO17)") (class "Default")
      (node (ref "SJ24") (pin "1") (pinfunction "1_1") (pintype "passive"))
      (node (ref "U1") (pin "28") (pinfunction "IO17_28") (pintype "bidirectional"))
    )
    (net (code "142") (name "Net-(U1-IO18)") (class "Default")
      (node (ref "SJ25") (pin "1") (pinfunction "1_1") (pintype "passive"))
      (node (ref "U1") (pin "30") (pinfunction "IO18_30") (pintype "bidirectional"))
    )
    (net (code "143") (name "Net-(VT1-TIP)") (class "Default")
      (node (ref "R43") (pin "2") (pinfunction "2_2") (pintype "passive"))
      (node (ref "VT1") (pin "PWR2") (pinfunction "TIP_PWR2") (pintype "bidirectional"))
    )
    (net (code "144") (name "Net-(VT2-TIP)") (class "Default")
      (node (ref "R42") (pin "2") (pinfunction "2_2") (pintype "passive"))
      (node (ref "VT2") (pin "PWR2") (pinfunction "TIP_PWR2") (pintype "bidirectional"))
    )
    (net (code "145") (name "Net-(VT3-TIP)") (class "Default")
      (node (ref "R41") (pin "1") (pinfunction "1_1") (pintype "passive"))
      (node (ref "VT3") (pin "PWR2") (pinfunction "TIP_PWR2") (pintype "bidirectional"))
    )
    (net (code "146") (name "unconnected-(CT1-3-PadP$3)") (class "Default")
      (node (ref "CT1") (pin "P$3") (pinfunction "3_P$3") (pintype "bidirectional"))
    )
    (net (code "147") (name "unconnected-(CT2-3-PadP$3)") (class "Default")
      (node (ref "CT2") (pin "P$3") (pinfunction "3_P$3") (pintype "bidirectional"))
    )
    (net (code "148") (name "unconnected-(CT3-3-PadP$3)") (class "Default")
      (node (ref "CT3") (pin "P$3") (pinfunction "3_P$3") (pintype "bidirectional"))
    )
    (net (code "149") (name "unconnected-(CT4-3-PadP$3)") (class "Default")
      (node (ref "CT4") (pin "P$3") (pinfunction "3_P$3") (pintype "bidirectional"))
    )
    (net (code "150") (name "unconnected-(CT5-3-PadP$3)") (class "Default")
      (node (ref "CT5") (pin "P$3") (pinfunction "3_P$3") (pintype "bidirectional"))
    )
    (net (code "151") (name "unconnected-(CT6-3-PadP$3)") (class "Default")
      (node (ref "CT6") (pin "P$3") (pinfunction "3_P$3") (pintype "bidirectional"))
    )
    (net (code "152") (name "unconnected-(CT7-3-PadP$3)") (class "Default")
      (node (ref "CT7") (pin "P$3") (pinfunction "3_P$3") (pintype "bidirectional"))
    )
    (net (code "153") (name "unconnected-(CT8-3-PadP$3)") (class "Default")
      (node (ref "CT8") (pin "P$3") (pinfunction "3_P$3") (pintype "bidirectional"))
    )
    (net (code "154") (name "unconnected-(CT9-3-PadP$3)") (class "Default")
      (node (ref "CT9") (pin "P$3") (pinfunction "3_P$3") (pintype "bidirectional"))
    )
    (net (code "155") (name "unconnected-(PCB2-3V3-PadP$41)") (class "Default")
      (node (ref "PCB2") (pin "P$41") (pinfunction "3V3_P$41") (pintype "bidirectional"))
    )
    (net (code "156") (name "unconnected-(PCB2-3V3-PadP$57)") (class "Default")
      (node (ref "PCB2") (pin "P$57") (pinfunction "3V3_P$57") (pintype "bidirectional"))
    )
    (net (code "157") (name "unconnected-(PCB2-GPIO2-PadP$43)") (class "Default")
      (node (ref "PCB2") (pin "P$43") (pinfunction "GPIO2_P$43") (pintype "bidirectional"))
    )
    (net (code "158") (name "unconnected-(PCB2-GPIO3-PadP$45)") (class "Default")
      (node (ref "PCB2") (pin "P$45") (pinfunction "GPIO3_P$45") (pintype "bidirectional"))
    )
    (net (code "159") (name "unconnected-(PCB2-GPIO6-PadP$71)") (class "Default")
      (node (ref "PCB2") (pin "P$71") (pinfunction "GPIO6_P$71") (pintype "bidirectional"))
    )
    (net (code "160") (name "unconnected-(PCB2-GPIO7-PadP$66)") (class "Default")
      (node (ref "PCB2") (pin "P$66") (pinfunction "GPIO7_P$66") (pintype "bidirectional"))
    )
    (net (code "161") (name "unconnected-(PCB2-GPIO13-PadP$73)") (class "Default")
      (node (ref "PCB2") (pin "P$73") (pinfunction "GPIO13_P$73") (pintype "bidirectional"))
    )
    (net (code "162") (name "unconnected-(PCB2-GPIO19-PadP$75)") (class "Default")
      (node (ref "PCB2") (pin "P$75") (pinfunction "GPIO19_P$75") (pintype "bidirectional"))
    )
    (net (code "163") (name "unconnected-(PCB2-GPIO21-PadP$80)") (class "Default")
      (node (ref "PCB2") (pin "P$80") (pinfunction "GPIO21_P$80") (pintype "bidirectional"))
    )
    (net (code "164") (name "unconnected-(PCB2-GPIO22-PadP$55)") (class "Default")
      (node (ref "PCB2") (pin "P$55") (pinfunction "GPIO22_P$55") (pintype "bidirectional"))
    )
    (net (code "165") (name "unconnected-(PCB2-GPIO25-PadP$62)") (class "Default")
      (node (ref "PCB2") (pin "P$62") (pinfunction "GPIO25_P$62") (pintype "bidirectional"))
    )
    (net (code "166") (name "unconnected-(PCB2-GPIO26-PadP$77)") (class "Default")
      (node (ref "PCB2") (pin "P$77") (pinfunction "GPIO26_P$77") (pintype "bidirectional"))
    )
    (net (code "167") (name "unconnected-(RFM69HCW-CLK-Pad5)") (class "Default")
      (node (ref "RFM69HCW") (pin "5") (pinfunction "CLK_5") (pintype "output"))
    )
    (net (code "168") (name "unconnected-(RFM69HCW-DCLK{slash}CFIL{slash}FFIT-Pad4)") (class "Default")
      (node (ref "RFM69HCW") (pin "4") (pinfunction "DCLK/CFIL/FFIT_4") (pintype "bidirectional"))
    )
    (net (code "169") (name "unconnected-(RFM69HCW-FSK{slash}DATA{slash}NFFS-Pad3)") (class "Default")
      (node (ref "RFM69HCW") (pin "3") (pinfunction "FSK/DATA/NFFS_3") (pintype "bidirectional"))
    )
    (net (code "170") (name "unconnected-(RFM69HCW-~{INT}-Pad11)") (class "Default")
      (node (ref "RFM69HCW") (pin "11") (pinfunction "~{INT}_11") (pintype "bidirectional"))
    )
    (net (code "171") (name "unconnected-(STM32F303VE-PB2-Pad37)") (class "Default")
      (node (ref "STM32F303VE") (pin "37") (pinfunction "PB2_37") (pintype "bidirectional"))
    )
    (net (code "172") (name "unconnected-(STM32F303VE-PB4-Pad90)") (class "Default")
      (node (ref "STM32F303VE") (pin "90") (pinfunction "PB4_90") (pintype "bidirectional"))
    )
    (net (code "173") (name "unconnected-(STM32F303VE-PB13-Pad52)") (class "Default")
      (node (ref "STM32F303VE") (pin "52") (pinfunction "PB13_52") (pintype "bidirectional"))
    )
    (net (code "174") (name "unconnected-(STM32F303VE-PC5-Pad34)") (class "Default")
      (node (ref "STM32F303VE") (pin "34") (pinfunction "PC5_34") (pintype "bidirectional"))
    )
    (net (code "175") (name "unconnected-(STM32F303VE-PC13-Pad7)") (class "Default")
      (node (ref "STM32F303VE") (pin "7") (pinfunction "PC13_7") (pintype "bidirectional"))
    )
    (net (code "176") (name "unconnected-(STM32F303VE-PD1-Pad82)") (class "Default")
      (node (ref "STM32F303VE") (pin "82") (pinfunction "PD1_82") (pintype "bidirectional"))
    )
    (net (code "177") (name "unconnected-(STM32F303VE-PD2-Pad83)") (class "Default")
      (node (ref "STM32F303VE") (pin "83") (pinfunction "PD2_83") (pintype "bidirectional"))
    )
    (net (code "178") (name "unconnected-(STM32F303VE-PD4-Pad85)") (class "Default")
      (node (ref "STM32F303VE") (pin "85") (pinfunction "PD4_85") (pintype "bidirectional"))
    )
    (net (code "179") (name "unconnected-(STM32F303VE-PD6-Pad87)") (class "Default")
      (node (ref "STM32F303VE") (pin "87") (pinfunction "PD6_87") (pintype "bidirectional"))
    )
    (net (code "180") (name "unconnected-(STM32F303VE-PD7-Pad88)") (class "Default")
      (node (ref "STM32F303VE") (pin "88") (pinfunction "PD7_88") (pintype "bidirectional"))
    )
    (net (code "181") (name "unconnected-(STM32F303VE-PD14-Pad61)") (class "Default")
      (node (ref "STM32F303VE") (pin "61") (pinfunction "PD14_61") (pintype "bidirectional"))
    )
    (net (code "182") (name "unconnected-(STM32F303VE-PD15-Pad62)") (class "Default")
      (node (ref "STM32F303VE") (pin "62") (pinfunction "PD15_62") (pintype "bidirectional"))
    )
    (net (code "183") (name "unconnected-(STM32F303VE-PE14-Pad45)") (class "Default")
      (node (ref "STM32F303VE") (pin "45") (pinfunction "PE14_45") (pintype "bidirectional"))
    )
    (net (code "184") (name "unconnected-(STM32F303VE-PE15-Pad46)") (class "Default")
      (node (ref "STM32F303VE") (pin "46") (pinfunction "PE15_46") (pintype "bidirectional"))
    )
    (net (code "185") (name "unconnected-(STM32F303VE-PF6-Pad73)") (class "Default")
      (node (ref "STM32F303VE") (pin "73") (pinfunction "PF6_73") (pintype "bidirectional"))
    )
    (net (code "186") (name "unconnected-(STM32F303VE-PF9-Pad10)") (class "Default")
      (node (ref "STM32F303VE") (pin "10") (pinfunction "PF9_10") (pintype "bidirectional"))
    )
    (net (code "187") (name "unconnected-(STM32F303VE-PF10-Pad11)") (class "Default")
      (node (ref "STM32F303VE") (pin "11") (pinfunction "PF10_11") (pintype "bidirectional"))
    )
    (net (code "188") (name "unconnected-(SV2-Pad2)") (class "Default")
      (node (ref "SV2") (pin "2") (pinfunction "2_2") (pintype "passive"))
    )
    (net (code "189") (name "unconnected-(U1-IO4-Pad26)") (class "Default")
      (node (ref "U1") (pin "26") (pinfunction "IO4_26") (pintype "bidirectional"))
    )
    (net (code "190") (name "unconnected-(U1-IO5-Pad29)") (class "Default")
      (node (ref "U1") (pin "29") (pinfunction "IO5_29") (pintype "bidirectional"))
    )
    (net (code "191") (name "unconnected-(U1-IO23-Pad37)") (class "Default")
      (node (ref "U1") (pin "37") (pinfunction "IO23_37") (pintype "bidirectional"))
    )
    (net (code "192") (name "unconnected-(U1-IO25-Pad10)") (class "Default")
      (node (ref "U1") (pin "10") (pinfunction "IO25_10") (pintype "bidirectional"))
    )
    (net (code "193") (name "unconnected-(U1-IO26-Pad11)") (class "Default")
      (node (ref "U1") (pin "11") (pinfunction "IO26_11") (pintype "bidirectional"))
    )
    (net (code "194") (name "unconnected-(U1-IO27-Pad12)") (class "Default")
      (node (ref "U1") (pin "12") (pinfunction "IO27_12") (pintype "bidirectional"))
    )
    (net (code "195") (name "unconnected-(U1-IO32-Pad8)") (class "Default")
      (node (ref "U1") (pin "8") (pinfunction "IO32_8") (pintype "bidirectional"))
    )
    (net (code "196") (name "unconnected-(U1-IO33-Pad9)") (class "Default")
      (node (ref "U1") (pin "9") (pinfunction "IO33_9") (pintype "bidirectional"))
    )
    (net (code "197") (name "unconnected-(U1-IO34-Pad6)") (class "Default")
      (node (ref "U1") (pin "6") (pinfunction "IO34_6") (pintype "bidirectional"))
    )
    (net (code "198") (name "unconnected-(U1-IO35-Pad7)") (class "Default")
      (node (ref "U1") (pin "7") (pinfunction "IO35_7") (pintype "bidirectional"))
    )
    (net (code "199") (name "unconnected-(U1-SCL{slash}CLK-Pad20)") (class "Default")
      (node (ref "U1") (pin "20") (pinfunction "SCL/CLK_20") (pintype "bidirectional"))
    )
    (net (code "200") (name "unconnected-(U1-SCS{slash}CMD-Pad19)") (class "Default")
      (node (ref "U1") (pin "19") (pinfunction "SCS/CMD_19") (pintype "bidirectional"))
    )
    (net (code "201") (name "unconnected-(U1-SDI{slash}SD1-Pad22)") (class "Default")
      (node (ref "U1") (pin "22") (pinfunction "SDI/SD1_22") (pintype "bidirectional"))
    )
    (net (code "202") (name "unconnected-(U1-SDO{slash}SD0-Pad21)") (class "Default")
      (node (ref "U1") (pin "21") (pinfunction "SDO/SD0_21") (pintype "bidirectional"))
    )
    (net (code "203") (name "unconnected-(U1-SENSOR_VN-Pad5)") (class "Default")
      (node (ref "U1") (pin "5") (pinfunction "SENSOR_VN_5") (pintype "input"))
    )
    (net (code "204") (name "unconnected-(U1-SENSOR_VP-Pad4)") (class "Default")
      (node (ref "U1") (pin "4") (pinfunction "SENSOR_VP_4") (pintype "input"))
    )
    (net (code "205") (name "unconnected-(U1-SHD{slash}SD2-Pad17)") (class "Default")
      (node (ref "U1") (pin "17") (pinfunction "SHD/SD2_17") (pintype "bidirectional"))
    )
    (net (code "206") (name "unconnected-(U1-SWP{slash}SD3-Pad18)") (class "Default")
      (node (ref "U1") (pin "18") (pinfunction "SWP/SD3_18") (pintype "bidirectional"))
    )
  )
)
